# ElectronThingyStick.net
KiCad netlist of a schematic drawn in EAGLE
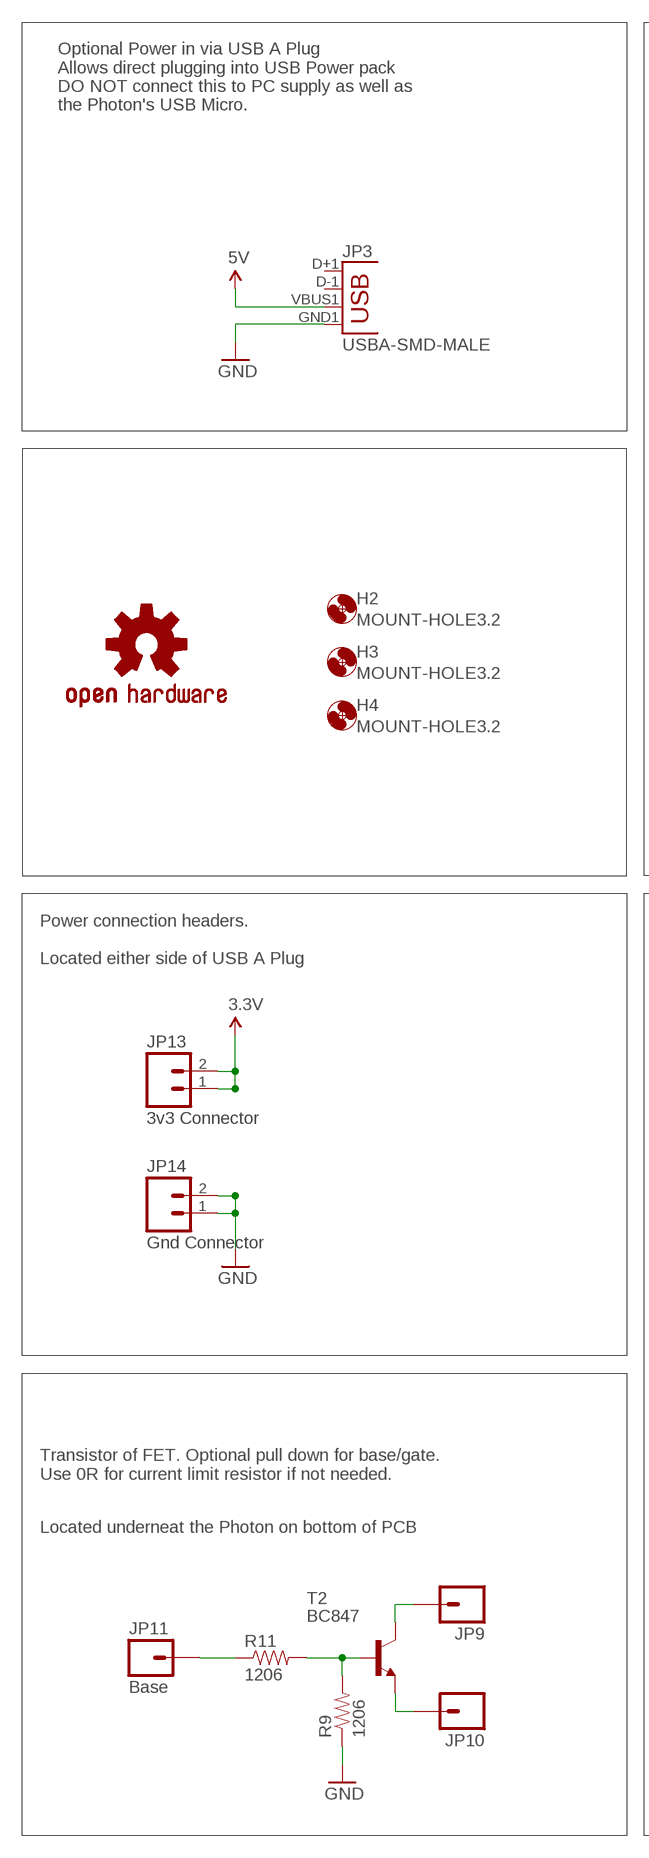
[diagram p0: schematic, sheet 1, part 1 of 2]
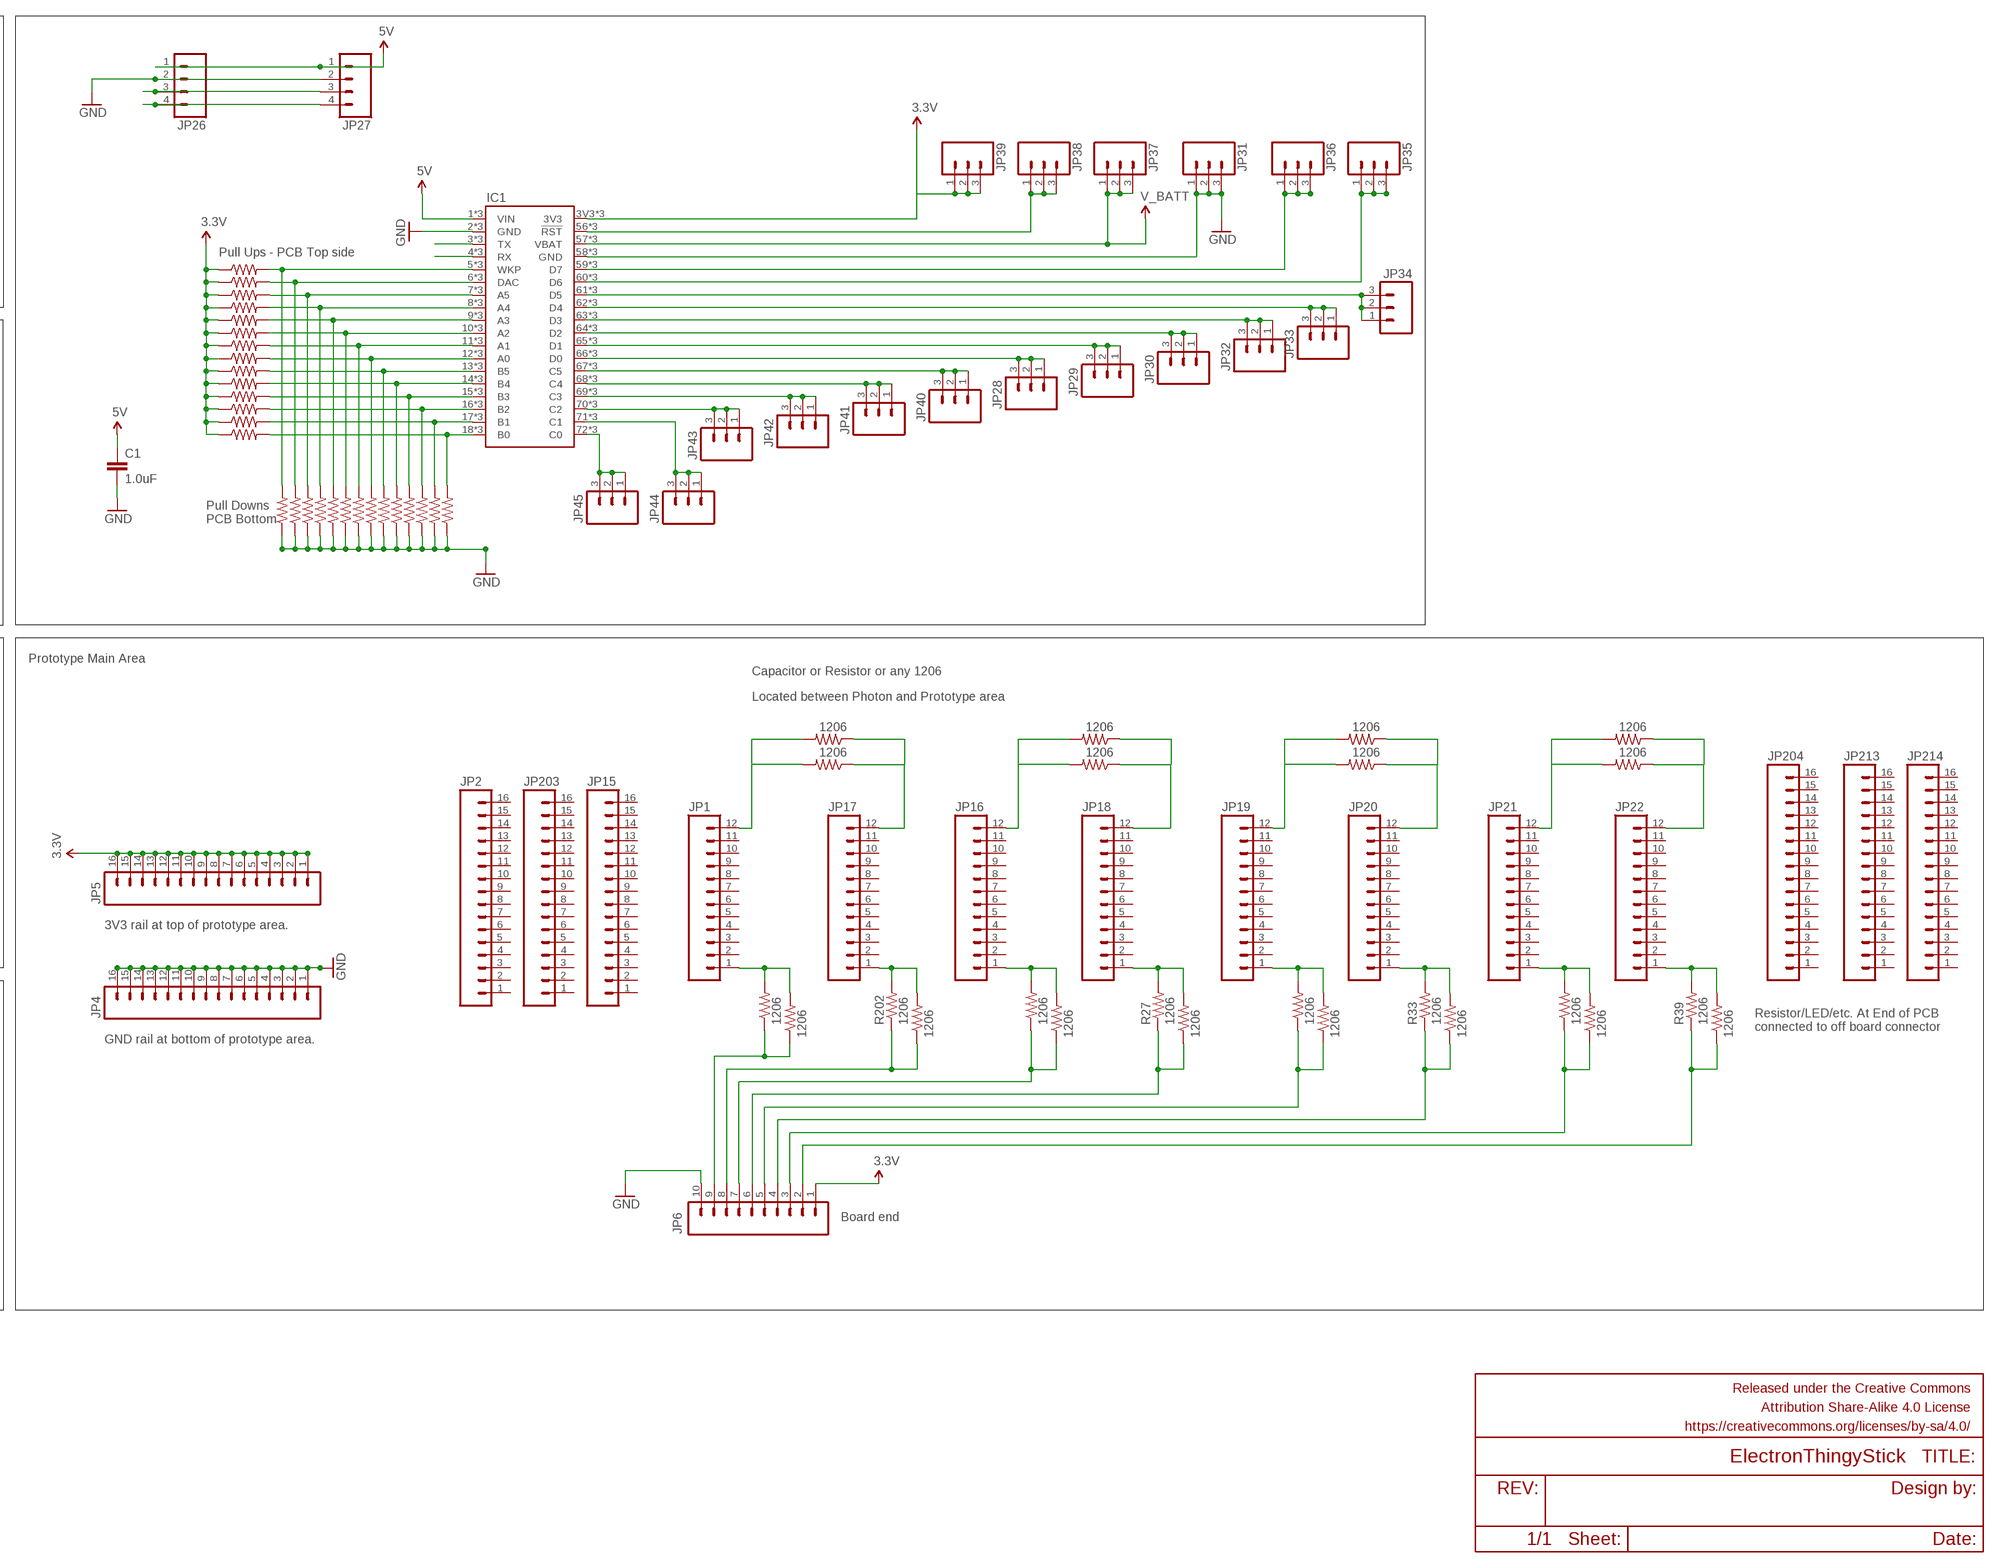
[diagram p1: schematic, sheet 1, part 2 of 2]

(export (version "E")
  (design (tool "Eeschema 10.0.6"))
  (components
    (comp (ref "C1")
      (value "1.0uF")
      (footprint "eagle-import:0805-CAP")
      (libsource (lib "eagle-import") (part "1.0UF-25V-+80/-20(0805){dblquote}"))
    )
    (comp (ref "FRAME1")
      (value "FRAME-LEDGER")
      (footprint "eagle-import:CREATIVE_COMMONS")
      (libsource (lib "eagle-import") (part "FRAME-LEDGER"))
    )
    (comp (ref "H2")
      (value "MOUNT-HOLE3.2")
      (footprint "eagle-import:3,2")
      (libsource (lib "eagle-import") (part "MOUNT-HOLE3.2"))
    )
    (comp (ref "H3")
      (value "MOUNT-HOLE3.2")
      (footprint "eagle-import:3,2")
      (libsource (lib "eagle-import") (part "MOUNT-HOLE3.2"))
    )
    (comp (ref "H4")
      (value "MOUNT-HOLE3.2")
      (footprint "eagle-import:3,2")
      (libsource (lib "eagle-import") (part "MOUNT-HOLE3.2"))
    )
    (comp (ref "IC1")
      (value "ELECTRONDUALROW")
      (footprint "eagle-import:ELECTRON_DUAL-ROW")
      (libsource (lib "eagle-import") (part "ELECTRONDUALROW"))
    )
    (comp (ref "JP1")
      (value "M12NO_SILK")
      (footprint "eagle-import:1X12_NO_SILK")
      (libsource (lib "eagle-import") (part "M12NO_SILK"))
    )
    (comp (ref "JP2")
      (value "M161X16_NO_SILK")
      (footprint "eagle-import:1X16_NO_SILK")
      (libsource (lib "eagle-import") (part "M161X16_NO_SILK"))
    )
    (comp (ref "JP3")
      (value "USBA-SMD-MALE")
      (footprint "eagle-import:USB-A-SMT-MALE")
      (libsource (lib "eagle-import") (part "USBA-SMD-MALE"))
    )
    (comp (ref "JP4")
      (value "M16PTH")
      (footprint "eagle-import:1X16")
      (libsource (lib "eagle-import") (part "M16PTH"))
    )
    (comp (ref "JP5")
      (value "M16PTH")
      (footprint "eagle-import:1X16")
      (libsource (lib "eagle-import") (part "M16PTH"))
    )
    (comp (ref "JP6")
      (value "M10NO_SILK_PTH_FEMALE")
      (footprint "eagle-import:1X10_NO_SILK")
      (libsource (lib "eagle-import") (part "M10NO_SILK_PTH_FEMALE"))
    )
    (comp (ref "JP9")
      (value "M01PTH")
      (footprint "eagle-import:1X01")
      (libsource (lib "eagle-import") (part "M01PTH"))
    )
    (comp (ref "JP10")
      (value "M01PTH")
      (footprint "eagle-import:1X01")
      (libsource (lib "eagle-import") (part "M01PTH"))
    )
    (comp (ref "JP11")
      (value "Base")
      (footprint "eagle-import:1X01")
      (libsource (lib "eagle-import") (part "M01PTH"))
    )
    (comp (ref "JP13")
      (value "3v3 Connector")
      (footprint "eagle-import:1X02")
      (libsource (lib "eagle-import") (part "M02PTH"))
    )
    (comp (ref "JP14")
      (value "Gnd Connector")
      (footprint "eagle-import:1X02")
      (libsource (lib "eagle-import") (part "M02PTH"))
    )
    (comp (ref "JP15")
      (value "M161X16_NO_SILK")
      (footprint "eagle-import:1X16_NO_SILK")
      (libsource (lib "eagle-import") (part "M161X16_NO_SILK"))
    )
    (comp (ref "JP16")
      (value "M12NO_SILK")
      (footprint "eagle-import:1X12_NO_SILK")
      (libsource (lib "eagle-import") (part "M12NO_SILK"))
    )
    (comp (ref "JP17")
      (value "M12NO_SILK")
      (footprint "eagle-import:1X12_NO_SILK")
      (libsource (lib "eagle-import") (part "M12NO_SILK"))
    )
    (comp (ref "JP18")
      (value "M12NO_SILK")
      (footprint "eagle-import:1X12_NO_SILK")
      (libsource (lib "eagle-import") (part "M12NO_SILK"))
    )
    (comp (ref "JP19")
      (value "M12NO_SILK")
      (footprint "eagle-import:1X12_NO_SILK")
      (libsource (lib "eagle-import") (part "M12NO_SILK"))
    )
    (comp (ref "JP20")
      (value "M12NO_SILK")
      (footprint "eagle-import:1X12_NO_SILK")
      (libsource (lib "eagle-import") (part "M12NO_SILK"))
    )
    (comp (ref "JP21")
      (value "M12NO_SILK")
      (footprint "eagle-import:1X12_NO_SILK")
      (libsource (lib "eagle-import") (part "M12NO_SILK"))
    )
    (comp (ref "JP22")
      (value "M12NO_SILK")
      (footprint "eagle-import:1X12_NO_SILK")
      (libsource (lib "eagle-import") (part "M12NO_SILK"))
    )
    (comp (ref "JP26")
      (value "M041X04_NO_SILK")
      (footprint "eagle-import:1X04_NO_SILK")
      (libsource (lib "eagle-import") (part "M041X04_NO_SILK"))
    )
    (comp (ref "JP27")
      (value "M041X04_NO_SILK")
      (footprint "eagle-import:1X04_NO_SILK")
      (libsource (lib "eagle-import") (part "M041X04_NO_SILK"))
    )
    (comp (ref "JP28")
      (value "M03PTH")
      (footprint "eagle-import:1X03")
      (libsource (lib "eagle-import") (part "M03PTH"))
    )
    (comp (ref "JP29")
      (value "M03PTH")
      (footprint "eagle-import:1X03")
      (libsource (lib "eagle-import") (part "M03PTH"))
    )
    (comp (ref "JP30")
      (value "M03PTH")
      (footprint "eagle-import:1X03")
      (libsource (lib "eagle-import") (part "M03PTH"))
    )
    (comp (ref "JP31")
      (value "M03PTH")
      (footprint "eagle-import:1X03")
      (libsource (lib "eagle-import") (part "M03PTH"))
    )
    (comp (ref "JP32")
      (value "M03PTH")
      (footprint "eagle-import:1X03")
      (libsource (lib "eagle-import") (part "M03PTH"))
    )
    (comp (ref "JP33")
      (value "M03PTH")
      (footprint "eagle-import:1X03")
      (libsource (lib "eagle-import") (part "M03PTH"))
    )
    (comp (ref "JP34")
      (value "M03PTH")
      (footprint "eagle-import:1X03")
      (libsource (lib "eagle-import") (part "M03PTH"))
    )
    (comp (ref "JP35")
      (value "M03PTH")
      (footprint "eagle-import:1X03")
      (libsource (lib "eagle-import") (part "M03PTH"))
    )
    (comp (ref "JP36")
      (value "M03PTH")
      (footprint "eagle-import:1X03")
      (libsource (lib "eagle-import") (part "M03PTH"))
    )
    (comp (ref "JP37")
      (value "M03PTH")
      (footprint "eagle-import:1X03")
      (libsource (lib "eagle-import") (part "M03PTH"))
    )
    (comp (ref "JP38")
      (value "M03PTH")
      (footprint "eagle-import:1X03")
      (libsource (lib "eagle-import") (part "M03PTH"))
    )
    (comp (ref "JP39")
      (value "M03PTH")
      (footprint "eagle-import:1X03")
      (libsource (lib "eagle-import") (part "M03PTH"))
    )
    (comp (ref "JP40")
      (value "M03PTH")
      (footprint "eagle-import:1X03")
      (libsource (lib "eagle-import") (part "M03PTH"))
    )
    (comp (ref "JP41")
      (value "M03PTH")
      (footprint "eagle-import:1X03")
      (libsource (lib "eagle-import") (part "M03PTH"))
    )
    (comp (ref "JP42")
      (value "M03PTH")
      (footprint "eagle-import:1X03")
      (libsource (lib "eagle-import") (part "M03PTH"))
    )
    (comp (ref "JP43")
      (value "M03PTH")
      (footprint "eagle-import:1X03")
      (libsource (lib "eagle-import") (part "M03PTH"))
    )
    (comp (ref "JP44")
      (value "M03PTH")
      (footprint "eagle-import:1X03")
      (libsource (lib "eagle-import") (part "M03PTH"))
    )
    (comp (ref "JP45")
      (value "M03PTH")
      (footprint "eagle-import:1X03")
      (libsource (lib "eagle-import") (part "M03PTH"))
    )
    (comp (ref "JP203")
      (value "M161X16_NO_SILK")
      (footprint "eagle-import:1X16_NO_SILK")
      (libsource (lib "eagle-import") (part "M161X16_NO_SILK"))
    )
    (comp (ref "JP204")
      (value "M161X16_NO_SILK")
      (footprint "eagle-import:1X16_NO_SILK")
      (libsource (lib "eagle-import") (part "M161X16_NO_SILK"))
    )
    (comp (ref "JP213")
      (value "M161X16_NO_SILK")
      (footprint "eagle-import:1X16_NO_SILK")
      (libsource (lib "eagle-import") (part "M161X16_NO_SILK"))
    )
    (comp (ref "JP214")
      (value "M161X16_NO_SILK")
      (footprint "eagle-import:1X16_NO_SILK")
      (libsource (lib "eagle-import") (part "M161X16_NO_SILK"))
    )
    (comp (ref "LOGO1")
      (value "OSHW-LOGOM")
      (footprint "eagle-import:OSHW-LOGO-M")
      (libsource (lib "eagle-import") (part "OSHW-LOGOM"))
    )
    (comp (ref "R1")
      (value "1206")
      (footprint "eagle-import:1206")
      (libsource (lib "eagle-import") (part "SparkFun-Resistors_RESISTOR1206"))
    )
    (comp (ref "R2")
      (value "1206")
      (footprint "eagle-import:1206")
      (libsource (lib "eagle-import") (part "SparkFun-Resistors_RESISTOR1206"))
    )
    (comp (ref "R3")
      (value "1206")
      (footprint "eagle-import:1206")
      (libsource (lib "eagle-import") (part "SparkFun-Resistors_RESISTOR1206"))
    )
    (comp (ref "R4")
      (value "1206")
      (footprint "eagle-import:1206")
      (libsource (lib "eagle-import") (part "SparkFun-Resistors_RESISTOR1206"))
    )
    (comp (ref "R5")
      (value "1206")
      (footprint "eagle-import:1206")
      (libsource (lib "eagle-import") (part "SparkFun-Resistors_RESISTOR1206"))
    )
    (comp (ref "R6")
      (value "1206")
      (footprint "eagle-import:1206")
      (libsource (lib "eagle-import") (part "SparkFun-Resistors_RESISTOR1206"))
    )
    (comp (ref "R7")
      (value "1206")
      (footprint "eagle-import:1206")
      (libsource (lib "eagle-import") (part "SparkFun-Resistors_RESISTOR1206"))
    )
    (comp (ref "R8")
      (value "1206")
      (footprint "eagle-import:1206")
      (libsource (lib "eagle-import") (part "SparkFun-Resistors_RESISTOR1206"))
    )
    (comp (ref "R9")
      (value "1206")
      (footprint "eagle-import:1206")
      (libsource (lib "eagle-import") (part "RESISTOR1206"))
    )
    (comp (ref "R10")
      (value "1206")
      (footprint "eagle-import:1206")
      (libsource (lib "eagle-import") (part "SparkFun-Resistors_RESISTOR1206"))
    )
    (comp (ref "R11")
      (value "1206")
      (footprint "eagle-import:1206")
      (libsource (lib "eagle-import") (part "RESISTOR1206"))
    )
    (comp (ref "R12")
      (value "1206")
      (footprint "eagle-import:1206")
      (libsource (lib "eagle-import") (part "SparkFun-Resistors_RESISTOR1206"))
    )
    (comp (ref "R13")
      (value "1206")
      (footprint "eagle-import:1206")
      (libsource (lib "eagle-import") (part "SparkFun-Resistors_RESISTOR1206"))
    )
    (comp (ref "R14")
      (value "1206")
      (footprint "eagle-import:1206")
      (libsource (lib "eagle-import") (part "SparkFun-Resistors_RESISTOR1206"))
    )
    (comp (ref "R15")
      (value "1206")
      (footprint "eagle-import:1206")
      (libsource (lib "eagle-import") (part "SparkFun-Resistors_RESISTOR1206"))
    )
    (comp (ref "R16")
      (value "1206")
      (footprint "eagle-import:1206")
      (libsource (lib "eagle-import") (part "SparkFun-Resistors_RESISTOR1206"))
    )
    (comp (ref "R17")
      (value "1206")
      (footprint "eagle-import:1206")
      (libsource (lib "eagle-import") (part "SparkFun-Resistors_RESISTOR1206"))
    )
    (comp (ref "R18")
      (value "1206")
      (footprint "eagle-import:1206")
      (libsource (lib "eagle-import") (part "SparkFun-Resistors_RESISTOR1206"))
    )
    (comp (ref "R19")
      (value "1206")
      (footprint "eagle-import:1206")
      (libsource (lib "eagle-import") (part "SparkFun-Resistors_RESISTOR1206"))
    )
    (comp (ref "R20")
      (value "1206")
      (footprint "eagle-import:1206")
      (libsource (lib "eagle-import") (part "SparkFun-Resistors_RESISTOR1206"))
    )
    (comp (ref "R21")
      (value "1206")
      (footprint "eagle-import:1206")
      (libsource (lib "eagle-import") (part "SparkFun-Resistors_RESISTOR1206"))
    )
    (comp (ref "R22")
      (value "1206")
      (footprint "eagle-import:1206")
      (libsource (lib "eagle-import") (part "SparkFun-Resistors_RESISTOR1206"))
    )
    (comp (ref "R23")
      (value "1206")
      (footprint "eagle-import:1206")
      (libsource (lib "eagle-import") (part "SparkFun-Resistors_RESISTOR1206"))
    )
    (comp (ref "R24")
      (value "1206")
      (footprint "eagle-import:1206")
      (libsource (lib "eagle-import") (part "SparkFun-Resistors_RESISTOR1206"))
    )
    (comp (ref "R25")
      (value "1206")
      (footprint "eagle-import:1206")
      (libsource (lib "eagle-import") (part "SparkFun-Resistors_RESISTOR1206"))
    )
    (comp (ref "R26")
      (value "1206")
      (footprint "eagle-import:1206")
      (libsource (lib "eagle-import") (part "SparkFun-Resistors_RESISTOR1206"))
    )
    (comp (ref "R27")
      (value "1206")
      (footprint "eagle-import:1206")
      (libsource (lib "eagle-import") (part "SparkFun-Resistors_RESISTOR1206"))
    )
    (comp (ref "R28")
      (value "1206")
      (footprint "eagle-import:1206")
      (libsource (lib "eagle-import") (part "SparkFun-Resistors_RESISTOR1206"))
    )
    (comp (ref "R29")
      (value "1206")
      (footprint "eagle-import:1206")
      (libsource (lib "eagle-import") (part "SparkFun-Resistors_RESISTOR1206"))
    )
    (comp (ref "R30")
      (value "1206")
      (footprint "eagle-import:1206")
      (libsource (lib "eagle-import") (part "SparkFun-Resistors_RESISTOR1206"))
    )
    (comp (ref "R31")
      (value "1206")
      (footprint "eagle-import:1206")
      (libsource (lib "eagle-import") (part "SparkFun-Resistors_RESISTOR1206"))
    )
    (comp (ref "R32")
      (value "1206")
      (footprint "eagle-import:1206")
      (libsource (lib "eagle-import") (part "SparkFun-Resistors_RESISTOR1206"))
    )
    (comp (ref "R33")
      (value "1206")
      (footprint "eagle-import:1206")
      (libsource (lib "eagle-import") (part "SparkFun-Resistors_RESISTOR1206"))
    )
    (comp (ref "R34")
      (value "1206")
      (footprint "eagle-import:1206")
      (libsource (lib "eagle-import") (part "SparkFun-Resistors_RESISTOR1206"))
    )
    (comp (ref "R35")
      (value "1206")
      (footprint "eagle-import:1206")
      (libsource (lib "eagle-import") (part "SparkFun-Resistors_RESISTOR1206"))
    )
    (comp (ref "R36")
      (value "1206")
      (footprint "eagle-import:1206")
      (libsource (lib "eagle-import") (part "SparkFun-Resistors_RESISTOR1206"))
    )
    (comp (ref "R37")
      (value "1206")
      (footprint "eagle-import:1206")
      (libsource (lib "eagle-import") (part "SparkFun-Resistors_RESISTOR1206"))
    )
    (comp (ref "R38")
      (value "1206")
      (footprint "eagle-import:1206")
      (libsource (lib "eagle-import") (part "SparkFun-Resistors_RESISTOR1206"))
    )
    (comp (ref "R39")
      (value "1206")
      (footprint "eagle-import:1206")
      (libsource (lib "eagle-import") (part "SparkFun-Resistors_RESISTOR1206"))
    )
    (comp (ref "R40")
      (value "1206")
      (footprint "eagle-import:1206")
      (libsource (lib "eagle-import") (part "SparkFun-Resistors_RESISTOR1206"))
    )
    (comp (ref "R41")
      (value "1206")
      (footprint "eagle-import:1206")
      (libsource (lib "eagle-import") (part "SparkFun-Resistors_RESISTOR1206"))
    )
    (comp (ref "R42")
      (value "1206")
      (footprint "eagle-import:1206")
      (libsource (lib "eagle-import") (part "SparkFun-Resistors_RESISTOR1206"))
    )
    (comp (ref "R43")
      (value "1206")
      (footprint "eagle-import:1206")
      (libsource (lib "eagle-import") (part "SparkFun-Resistors_RESISTOR1206"))
    )
    (comp (ref "R44")
      (value "1206")
      (footprint "eagle-import:1206")
      (libsource (lib "eagle-import") (part "SparkFun-Resistors_RESISTOR1206"))
    )
    (comp (ref "R45")
      (value "1206")
      (footprint "eagle-import:1206")
      (libsource (lib "eagle-import") (part "SparkFun-Resistors_RESISTOR1206"))
    )
    (comp (ref "R46")
      (value "1206")
      (footprint "eagle-import:1206")
      (libsource (lib "eagle-import") (part "SparkFun-Resistors_RESISTOR1206"))
    )
    (comp (ref "R47")
      (value "1206")
      (footprint "eagle-import:1206")
      (libsource (lib "eagle-import") (part "SparkFun-Resistors_RESISTOR1206"))
    )
    (comp (ref "R48")
      (value "1206")
      (footprint "eagle-import:1206")
      (libsource (lib "eagle-import") (part "SparkFun-Resistors_RESISTOR1206"))
    )
    (comp (ref "R49")
      (value "1206")
      (footprint "eagle-import:1206")
      (libsource (lib "eagle-import") (part "SparkFun-Resistors_RESISTOR1206"))
    )
    (comp (ref "R50")
      (value "1206")
      (footprint "eagle-import:1206")
      (libsource (lib "eagle-import") (part "SparkFun-Resistors_RESISTOR1206"))
    )
    (comp (ref "R51")
      (value "1206")
      (footprint "eagle-import:1206")
      (libsource (lib "eagle-import") (part "SparkFun-Resistors_RESISTOR1206"))
    )
    (comp (ref "R52")
      (value "1206")
      (footprint "eagle-import:1206")
      (libsource (lib "eagle-import") (part "SparkFun-Resistors_RESISTOR1206"))
    )
    (comp (ref "R201")
      (value "1206")
      (footprint "eagle-import:1206")
      (libsource (lib "eagle-import") (part "SparkFun-Resistors_RESISTOR1206"))
    )
    (comp (ref "R202")
      (value "1206")
      (footprint "eagle-import:1206")
      (libsource (lib "eagle-import") (part "SparkFun-Resistors_RESISTOR1206"))
    )
    (comp (ref "T2")
      (value "BC847")
      (footprint "eagle-import:SOT23")
      (libsource (lib "eagle-import") (part "BC847"))
    )
  )
  (nets
    (net (code "1") (name "/RX") (class "Default")
      (node (ref "IC1") (pin "4") (pinfunction "RX_4") (pintype "bidirectional"))
      (node (ref "IC1") (pin "40") (pinfunction "RX_40") (pintype "bidirectional"))
      (node (ref "IC1") (pin "RX") (pinfunction "RX_RX") (pintype "bidirectional"))
      (node (ref "JP26") (pin "4") (pinfunction "4_4") (pintype "passive"))
      (node (ref "JP27") (pin "4") (pinfunction "4_4") (pintype "passive"))
    )
    (net (code "2") (name "/TX") (class "Default")
      (node (ref "IC1") (pin "3") (pinfunction "TX_3") (pintype "bidirectional"))
      (node (ref "IC1") (pin "39") (pinfunction "TX_39") (pintype "bidirectional"))
      (node (ref "IC1") (pin "TX") (pinfunction "TX_TX") (pintype "bidirectional"))
      (node (ref "JP26") (pin "3") (pinfunction "3_3") (pintype "passive"))
      (node (ref "JP27") (pin "3") (pinfunction "3_3") (pintype "passive"))
    )
    (net (code "3") (name "3.3V") (class "Default")
      (node (ref "IC1") (pin "3V3") (pinfunction "3V3_3V3") (pintype "power_in"))
      (node (ref "IC1") (pin "55") (pinfunction "3V3_55") (pintype "power_in"))
      (node (ref "IC1") (pin "91") (pinfunction "3V3_91") (pintype "power_in"))
      (node (ref "JP13") (pin "1") (pinfunction "1_1") (pintype "passive"))
      (node (ref "JP13") (pin "2") (pinfunction "2_2") (pintype "passive"))
      (node (ref "JP39") (pin "1") (pinfunction "1_1") (pintype "passive"))
      (node (ref "JP39") (pin "2") (pinfunction "2_2") (pintype "passive"))
      (node (ref "JP39") (pin "3") (pinfunction "3_3") (pintype "passive"))
      (node (ref "JP5") (pin "1") (pinfunction "1_1") (pintype "passive"))
      (node (ref "JP5") (pin "10") (pinfunction "10_10") (pintype "passive"))
      (node (ref "JP5") (pin "11") (pinfunction "11_11") (pintype "passive"))
      (node (ref "JP5") (pin "12") (pinfunction "12_12") (pintype "passive"))
      (node (ref "JP5") (pin "13") (pinfunction "13_13") (pintype "passive"))
      (node (ref "JP5") (pin "14") (pinfunction "14_14") (pintype "passive"))
      (node (ref "JP5") (pin "15") (pinfunction "15_15") (pintype "passive"))
      (node (ref "JP5") (pin "16") (pinfunction "16_16") (pintype "passive"))
      (node (ref "JP5") (pin "2") (pinfunction "2_2") (pintype "passive"))
      (node (ref "JP5") (pin "3") (pinfunction "3_3") (pintype "passive"))
      (node (ref "JP5") (pin "4") (pinfunction "4_4") (pintype "passive"))
      (node (ref "JP5") (pin "5") (pinfunction "5_5") (pintype "passive"))
      (node (ref "JP5") (pin "6") (pinfunction "6_6") (pintype "passive"))
      (node (ref "JP5") (pin "7") (pinfunction "7_7") (pintype "passive"))
      (node (ref "JP5") (pin "8") (pinfunction "8_8") (pintype "passive"))
      (node (ref "JP5") (pin "9") (pinfunction "9_9") (pintype "passive"))
      (node (ref "JP6") (pin "1") (pinfunction "1_1") (pintype "passive"))
      (node (ref "R1") (pin "1") (pinfunction "1_1") (pintype "passive"))
      (node (ref "R12") (pin "1") (pinfunction "1_1") (pintype "passive"))
      (node (ref "R15") (pin "1") (pinfunction "1_1") (pintype "passive"))
      (node (ref "R16") (pin "1") (pinfunction "1_1") (pintype "passive"))
      (node (ref "R17") (pin "1") (pinfunction "1_1") (pintype "passive"))
      (node (ref "R18") (pin "1") (pinfunction "1_1") (pintype "passive"))
      (node (ref "R2") (pin "1") (pinfunction "1_1") (pintype "passive"))
      (node (ref "R3") (pin "1") (pinfunction "1_1") (pintype "passive"))
      (node (ref "R4") (pin "1") (pinfunction "1_1") (pintype "passive"))
      (node (ref "R45") (pin "1") (pinfunction "1_1") (pintype "passive"))
      (node (ref "R46") (pin "1") (pinfunction "1_1") (pintype "passive"))
      (node (ref "R5") (pin "1") (pinfunction "1_1") (pintype "passive"))
      (node (ref "R6") (pin "1") (pinfunction "1_1") (pintype "passive"))
      (node (ref "R7") (pin "1") (pinfunction "1_1") (pintype "passive"))
    )
    (net (code "4") (name "5V") (class "Default")
      (node (ref "C1") (pin "1") (pinfunction "1_1") (pintype "passive"))
      (node (ref "IC1") (pin "1") (pinfunction "VIN_1") (pintype "power_in"))
      (node (ref "IC1") (pin "37") (pinfunction "VIN_37") (pintype "power_in"))
      (node (ref "IC1") (pin "VIN") (pinfunction "VIN_VIN") (pintype "power_in"))
      (node (ref "JP26") (pin "1") (pinfunction "1_1") (pintype "passive"))
      (node (ref "JP27") (pin "1") (pinfunction "1_1") (pintype "passive"))
      (node (ref "JP3") (pin "VBUS1") (pinfunction "VBUS_VBUS1") (pintype "bidirectional"))
    )
    (net (code "5") (name "GND") (class "Default")
      (node (ref "C1") (pin "2") (pinfunction "2_2") (pintype "passive"))
      (node (ref "IC1") (pin "2") (pinfunction "GND_2") (pintype "power_in"))
      (node (ref "IC1") (pin "38") (pinfunction "GND_38") (pintype "power_in"))
      (node (ref "IC1") (pin "58") (pinfunction "GND_58") (pintype "power_in"))
      (node (ref "IC1") (pin "94") (pinfunction "GND_94") (pintype "power_in"))
      (node (ref "IC1") (pin "GND") (pinfunction "GND_GND") (pintype "power_in"))
      (node (ref "IC1") (pin "GND@2") (pinfunction "GND_GND@2") (pintype "power_in"))
      (node (ref "JP14") (pin "1") (pinfunction "1_1") (pintype "passive"))
      (node (ref "JP14") (pin "2") (pinfunction "2_2") (pintype "passive"))
      (node (ref "JP26") (pin "2") (pinfunction "2_2") (pintype "passive"))
      (node (ref "JP27") (pin "2") (pinfunction "2_2") (pintype "passive"))
      (node (ref "JP3") (pin "GND1") (pinfunction "GND_GND1") (pintype "bidirectional"))
      (node (ref "JP31") (pin "1") (pinfunction "1_1") (pintype "passive"))
      (node (ref "JP31") (pin "2") (pinfunction "2_2") (pintype "passive"))
      (node (ref "JP31") (pin "3") (pinfunction "3_3") (pintype "passive"))
      (node (ref "JP4") (pin "1") (pinfunction "1_1") (pintype "passive"))
      (node (ref "JP4") (pin "10") (pinfunction "10_10") (pintype "passive"))
      (node (ref "JP4") (pin "11") (pinfunction "11_11") (pintype "passive"))
      (node (ref "JP4") (pin "12") (pinfunction "12_12") (pintype "passive"))
      (node (ref "JP4") (pin "13") (pinfunction "13_13") (pintype "passive"))
      (node (ref "JP4") (pin "14") (pinfunction "14_14") (pintype "passive"))
      (node (ref "JP4") (pin "15") (pinfunction "15_15") (pintype "passive"))
      (node (ref "JP4") (pin "16") (pinfunction "16_16") (pintype "passive"))
      (node (ref "JP4") (pin "2") (pinfunction "2_2") (pintype "passive"))
      (node (ref "JP4") (pin "3") (pinfunction "3_3") (pintype "passive"))
      (node (ref "JP4") (pin "4") (pinfunction "4_4") (pintype "passive"))
      (node (ref "JP4") (pin "5") (pinfunction "5_5") (pintype "passive"))
      (node (ref "JP4") (pin "6") (pinfunction "6_6") (pintype "passive"))
      (node (ref "JP4") (pin "7") (pinfunction "7_7") (pintype "passive"))
      (node (ref "JP4") (pin "8") (pinfunction "8_8") (pintype "passive"))
      (node (ref "JP4") (pin "9") (pinfunction "9_9") (pintype "passive"))
      (node (ref "JP6") (pin "10") (pinfunction "10_10") (pintype "passive"))
      (node (ref "R10") (pin "1") (pinfunction "1_1") (pintype "passive"))
      (node (ref "R13") (pin "1") (pinfunction "1_1") (pintype "passive"))
      (node (ref "R14") (pin "1") (pinfunction "1_1") (pintype "passive"))
      (node (ref "R19") (pin "1") (pinfunction "1_1") (pintype "passive"))
      (node (ref "R20") (pin "1") (pinfunction "1_1") (pintype "passive"))
      (node (ref "R21") (pin "1") (pinfunction "1_1") (pintype "passive"))
      (node (ref "R22") (pin "1") (pinfunction "1_1") (pintype "passive"))
      (node (ref "R47") (pin "1") (pinfunction "1_1") (pintype "passive"))
      (node (ref "R48") (pin "1") (pinfunction "1_1") (pintype "passive"))
      (node (ref "R49") (pin "1") (pinfunction "1_1") (pintype "passive"))
      (node (ref "R50") (pin "1") (pinfunction "1_1") (pintype "passive"))
      (node (ref "R51") (pin "1") (pinfunction "1_1") (pintype "passive"))
      (node (ref "R52") (pin "1") (pinfunction "1_1") (pintype "passive"))
      (node (ref "R8") (pin "1") (pinfunction "1_1") (pintype "passive"))
      (node (ref "R9") (pin "1") (pinfunction "1_1") (pintype "passive"))
    )
    (net (code "6") (name "Net-(IC1-A0-Pad12)") (class "Default")
      (node (ref "IC1") (pin "12") (pinfunction "A0_12") (pintype "bidirectional"))
      (node (ref "IC1") (pin "48") (pinfunction "A0_48") (pintype "bidirectional"))
      (node (ref "IC1") (pin "A0") (pinfunction "A0_A0") (pintype "bidirectional"))
      (node (ref "R22") (pin "2") (pinfunction "2_2") (pintype "passive"))
      (node (ref "R7") (pin "2") (pinfunction "2_2") (pintype "passive"))
    )
    (net (code "7") (name "Net-(IC1-A1-Pad11)") (class "Default")
      (node (ref "IC1") (pin "11") (pinfunction "A1_11") (pintype "bidirectional"))
      (node (ref "IC1") (pin "47") (pinfunction "A1_47") (pintype "bidirectional"))
      (node (ref "IC1") (pin "A1") (pinfunction "A1_A1") (pintype "bidirectional"))
      (node (ref "R21") (pin "2") (pinfunction "2_2") (pintype "passive"))
      (node (ref "R6") (pin "2") (pinfunction "2_2") (pintype "passive"))
    )
    (net (code "8") (name "Net-(IC1-A2-Pad10)") (class "Default")
      (node (ref "IC1") (pin "10") (pinfunction "A2_10") (pintype "bidirectional"))
      (node (ref "IC1") (pin "46") (pinfunction "A2_46") (pintype "bidirectional"))
      (node (ref "IC1") (pin "A2") (pinfunction "A2_A2") (pintype "bidirectional"))
      (node (ref "R20") (pin "2") (pinfunction "2_2") (pintype "passive"))
      (node (ref "R4") (pin "2") (pinfunction "2_2") (pintype "passive"))
    )
    (net (code "9") (name "Net-(IC1-A3-Pad45)") (class "Default")
      (node (ref "IC1") (pin "45") (pinfunction "A3_45") (pintype "bidirectional"))
      (node (ref "IC1") (pin "9") (pinfunction "A3_9") (pintype "bidirectional"))
      (node (ref "IC1") (pin "A3") (pinfunction "A3_A3") (pintype "bidirectional"))
      (node (ref "R19") (pin "2") (pinfunction "2_2") (pintype "passive"))
      (node (ref "R3") (pin "2") (pinfunction "2_2") (pintype "passive"))
    )
    (net (code "10") (name "Net-(IC1-A4-Pad44)") (class "Default")
      (node (ref "IC1") (pin "44") (pinfunction "A4_44") (pintype "bidirectional"))
      (node (ref "IC1") (pin "8") (pinfunction "A4_8") (pintype "bidirectional"))
      (node (ref "IC1") (pin "A4") (pinfunction "A4_A4") (pintype "bidirectional"))
      (node (ref "R14") (pin "2") (pinfunction "2_2") (pintype "passive"))
      (node (ref "R2") (pin "2") (pinfunction "2_2") (pintype "passive"))
    )
    (net (code "11") (name "Net-(IC1-A5-Pad43)") (class "Default")
      (node (ref "IC1") (pin "43") (pinfunction "A5_43") (pintype "bidirectional"))
      (node (ref "IC1") (pin "7") (pinfunction "A5_7") (pintype "bidirectional"))
      (node (ref "IC1") (pin "A5") (pinfunction "A5_A5") (pintype "bidirectional"))
      (node (ref "R1") (pin "2") (pinfunction "2_2") (pintype "passive"))
      (node (ref "R13") (pin "2") (pinfunction "2_2") (pintype "passive"))
    )
    (net (code "12") (name "Net-(IC1-B0-Pad18)") (class "Default")
      (node (ref "IC1") (pin "18") (pinfunction "B0_18") (pintype "bidirectional"))
      (node (ref "IC1") (pin "54") (pinfunction "B0_54") (pintype "bidirectional"))
      (node (ref "IC1") (pin "B0") (pinfunction "B0_B0") (pintype "bidirectional"))
      (node (ref "R46") (pin "2") (pinfunction "2_2") (pintype "passive"))
      (node (ref "R52") (pin "2") (pinfunction "2_2") (pintype "passive"))
    )
    (net (code "13") (name "Net-(IC1-B1-Pad17)") (class "Default")
      (node (ref "IC1") (pin "17") (pinfunction "B1_17") (pintype "bidirectional"))
      (node (ref "IC1") (pin "53") (pinfunction "B1_53") (pintype "bidirectional"))
      (node (ref "IC1") (pin "B1") (pinfunction "B1_B1") (pintype "bidirectional"))
      (node (ref "R45") (pin "2") (pinfunction "2_2") (pintype "passive"))
      (node (ref "R51") (pin "2") (pinfunction "2_2") (pintype "passive"))
    )
    (net (code "14") (name "Net-(IC1-B2-Pad16)") (class "Default")
      (node (ref "IC1") (pin "16") (pinfunction "B2_16") (pintype "bidirectional"))
      (node (ref "IC1") (pin "52") (pinfunction "B2_52") (pintype "bidirectional"))
      (node (ref "IC1") (pin "B2") (pinfunction "B2_B2") (pintype "bidirectional"))
      (node (ref "R18") (pin "2") (pinfunction "2_2") (pintype "passive"))
      (node (ref "R50") (pin "2") (pinfunction "2_2") (pintype "passive"))
    )
    (net (code "15") (name "Net-(IC1-B3-Pad15)") (class "Default")
      (node (ref "IC1") (pin "15") (pinfunction "B3_15") (pintype "bidirectional"))
      (node (ref "IC1") (pin "51") (pinfunction "B3_51") (pintype "bidirectional"))
      (node (ref "IC1") (pin "B3") (pinfunction "B3_B3") (pintype "bidirectional"))
      (node (ref "R17") (pin "2") (pinfunction "2_2") (pintype "passive"))
      (node (ref "R49") (pin "2") (pinfunction "2_2") (pintype "passive"))
    )
    (net (code "16") (name "Net-(IC1-B4-Pad14)") (class "Default")
      (node (ref "IC1") (pin "14") (pinfunction "B4_14") (pintype "bidirectional"))
      (node (ref "IC1") (pin "50") (pinfunction "B4_50") (pintype "bidirectional"))
      (node (ref "IC1") (pin "B4") (pinfunction "B4_B4") (pintype "bidirectional"))
      (node (ref "R16") (pin "2") (pinfunction "2_2") (pintype "passive"))
      (node (ref "R48") (pin "2") (pinfunction "2_2") (pintype "passive"))
    )
    (net (code "17") (name "Net-(IC1-B5-Pad13)") (class "Default")
      (node (ref "IC1") (pin "13") (pinfunction "B5_13") (pintype "bidirectional"))
      (node (ref "IC1") (pin "49") (pinfunction "B5_49") (pintype "bidirectional"))
      (node (ref "IC1") (pin "B5") (pinfunction "B5_B5") (pintype "bidirectional"))
      (node (ref "R15") (pin "2") (pinfunction "2_2") (pintype "passive"))
      (node (ref "R47") (pin "2") (pinfunction "2_2") (pintype "passive"))
    )
    (net (code "18") (name "Net-(IC1-C0-Pad108)") (class "Default")
      (node (ref "IC1") (pin "108") (pinfunction "C0_108") (pintype "bidirectional"))
      (node (ref "IC1") (pin "72") (pinfunction "C0_72") (pintype "bidirectional"))
      (node (ref "IC1") (pin "C0") (pinfunction "C0_C0") (pintype "bidirectional"))
      (node (ref "JP45") (pin "1") (pinfunction "1_1") (pintype "passive"))
      (node (ref "JP45") (pin "2") (pinfunction "2_2") (pintype "passive"))
      (node (ref "JP45") (pin "3") (pinfunction "3_3") (pintype "passive"))
    )
    (net (code "19") (name "Net-(IC1-C1-Pad107)") (class "Default")
      (node (ref "IC1") (pin "107") (pinfunction "C1_107") (pintype "bidirectional"))
      (node (ref "IC1") (pin "71") (pinfunction "C1_71") (pintype "bidirectional"))
      (node (ref "IC1") (pin "C1") (pinfunction "C1_C1") (pintype "bidirectional"))
      (node (ref "JP44") (pin "1") (pinfunction "1_1") (pintype "passive"))
      (node (ref "JP44") (pin "2") (pinfunction "2_2") (pintype "passive"))
      (node (ref "JP44") (pin "3") (pinfunction "3_3") (pintype "passive"))
    )
    (net (code "20") (name "Net-(IC1-C2-Pad106)") (class "Default")
      (node (ref "IC1") (pin "106") (pinfunction "C2_106") (pintype "bidirectional"))
      (node (ref "IC1") (pin "70") (pinfunction "C2_70") (pintype "bidirectional"))
      (node (ref "IC1") (pin "C2") (pinfunction "C2_C2") (pintype "bidirectional"))
      (node (ref "JP43") (pin "1") (pinfunction "1_1") (pintype "passive"))
      (node (ref "JP43") (pin "2") (pinfunction "2_2") (pintype "passive"))
      (node (ref "JP43") (pin "3") (pinfunction "3_3") (pintype "passive"))
    )
    (net (code "21") (name "Net-(IC1-C3-Pad105)") (class "Default")
      (node (ref "IC1") (pin "105") (pinfunction "C3_105") (pintype "bidirectional"))
      (node (ref "IC1") (pin "69") (pinfunction "C3_69") (pintype "bidirectional"))
      (node (ref "IC1") (pin "C3") (pinfunction "C3_C3") (pintype "bidirectional"))
      (node (ref "JP42") (pin "1") (pinfunction "1_1") (pintype "passive"))
      (node (ref "JP42") (pin "2") (pinfunction "2_2") (pintype "passive"))
      (node (ref "JP42") (pin "3") (pinfunction "3_3") (pintype "passive"))
    )
    (net (code "22") (name "Net-(IC1-C4-Pad104)") (class "Default")
      (node (ref "IC1") (pin "104") (pinfunction "C4_104") (pintype "bidirectional"))
      (node (ref "IC1") (pin "68") (pinfunction "C4_68") (pintype "bidirectional"))
      (node (ref "IC1") (pin "C4") (pinfunction "C4_C4") (pintype "bidirectional"))
      (node (ref "JP41") (pin "1") (pinfunction "1_1") (pintype "passive"))
      (node (ref "JP41") (pin "2") (pinfunction "2_2") (pintype "passive"))
      (node (ref "JP41") (pin "3") (pinfunction "3_3") (pintype "passive"))
    )
    (net (code "23") (name "Net-(IC1-C5-Pad103)") (class "Default")
      (node (ref "IC1") (pin "103") (pinfunction "C5_103") (pintype "bidirectional"))
      (node (ref "IC1") (pin "67") (pinfunction "C5_67") (pintype "bidirectional"))
      (node (ref "IC1") (pin "C5") (pinfunction "C5_C5") (pintype "bidirectional"))
      (node (ref "JP40") (pin "1") (pinfunction "1_1") (pintype "passive"))
      (node (ref "JP40") (pin "2") (pinfunction "2_2") (pintype "passive"))
      (node (ref "JP40") (pin "3") (pinfunction "3_3") (pintype "passive"))
    )
    (net (code "24") (name "Net-(IC1-D0-Pad102)") (class "Default")
      (node (ref "IC1") (pin "102") (pinfunction "D0_102") (pintype "bidirectional"))
      (node (ref "IC1") (pin "66") (pinfunction "D0_66") (pintype "bidirectional"))
      (node (ref "IC1") (pin "D0") (pinfunction "D0_D0") (pintype "bidirectional"))
      (node (ref "JP28") (pin "1") (pinfunction "1_1") (pintype "passive"))
      (node (ref "JP28") (pin "2") (pinfunction "2_2") (pintype "passive"))
      (node (ref "JP28") (pin "3") (pinfunction "3_3") (pintype "passive"))
    )
    (net (code "25") (name "Net-(IC1-D1-Pad101)") (class "Default")
      (node (ref "IC1") (pin "101") (pinfunction "D1_101") (pintype "bidirectional"))
      (node (ref "IC1") (pin "65") (pinfunction "D1_65") (pintype "bidirectional"))
      (node (ref "IC1") (pin "D1") (pinfunction "D1_D1") (pintype "bidirectional"))
      (node (ref "JP29") (pin "1") (pinfunction "1_1") (pintype "passive"))
      (node (ref "JP29") (pin "2") (pinfunction "2_2") (pintype "passive"))
      (node (ref "JP29") (pin "3") (pinfunction "3_3") (pintype "passive"))
    )
    (net (code "26") (name "Net-(IC1-D2-Pad100)") (class "Default")
      (node (ref "IC1") (pin "100") (pinfunction "D2_100") (pintype "bidirectional"))
      (node (ref "IC1") (pin "64") (pinfunction "D2_64") (pintype "bidirectional"))
      (node (ref "IC1") (pin "D2") (pinfunction "D2_D2") (pintype "bidirectional"))
      (node (ref "JP30") (pin "1") (pinfunction "1_1") (pintype "passive"))
      (node (ref "JP30") (pin "2") (pinfunction "2_2") (pintype "passive"))
      (node (ref "JP30") (pin "3") (pinfunction "3_3") (pintype "passive"))
    )
    (net (code "27") (name "Net-(IC1-D3-Pad63)") (class "Default")
      (node (ref "IC1") (pin "63") (pinfunction "D3_63") (pintype "bidirectional"))
      (node (ref "IC1") (pin "99") (pinfunction "D3_99") (pintype "bidirectional"))
      (node (ref "IC1") (pin "D3") (pinfunction "D3_D3") (pintype "bidirectional"))
      (node (ref "JP32") (pin "1") (pinfunction "1_1") (pintype "passive"))
      (node (ref "JP32") (pin "2") (pinfunction "2_2") (pintype "passive"))
      (node (ref "JP32") (pin "3") (pinfunction "3_3") (pintype "passive"))
    )
    (net (code "28") (name "Net-(IC1-D4-Pad62)") (class "Default")
      (node (ref "IC1") (pin "62") (pinfunction "D4_62") (pintype "bidirectional"))
      (node (ref "IC1") (pin "98") (pinfunction "D4_98") (pintype "bidirectional"))
      (node (ref "IC1") (pin "D4") (pinfunction "D4_D4") (pintype "bidirectional"))
      (node (ref "JP33") (pin "1") (pinfunction "1_1") (pintype "passive"))
      (node (ref "JP33") (pin "2") (pinfunction "2_2") (pintype "passive"))
      (node (ref "JP33") (pin "3") (pinfunction "3_3") (pintype "passive"))
    )
    (net (code "29") (name "Net-(IC1-D5-Pad61)") (class "Default")
      (node (ref "IC1") (pin "61") (pinfunction "D5_61") (pintype "bidirectional"))
      (node (ref "IC1") (pin "97") (pinfunction "D5_97") (pintype "bidirectional"))
      (node (ref "IC1") (pin "D5") (pinfunction "D5_D5") (pintype "bidirectional"))
      (node (ref "JP34") (pin "1") (pinfunction "1_1") (pintype "passive"))
      (node (ref "JP34") (pin "2") (pinfunction "2_2") (pintype "passive"))
      (node (ref "JP34") (pin "3") (pinfunction "3_3") (pintype "passive"))
    )
    (net (code "30") (name "Net-(IC1-D6-Pad60)") (class "Default")
      (node (ref "IC1") (pin "60") (pinfunction "D6_60") (pintype "bidirectional"))
      (node (ref "IC1") (pin "96") (pinfunction "D6_96") (pintype "bidirectional"))
      (node (ref "IC1") (pin "D6") (pinfunction "D6_D6") (pintype "bidirectional"))
      (node (ref "JP35") (pin "1") (pinfunction "1_1") (pintype "passive"))
      (node (ref "JP35") (pin "2") (pinfunction "2_2") (pintype "passive"))
      (node (ref "JP35") (pin "3") (pinfunction "3_3") (pintype "passive"))
    )
    (net (code "31") (name "Net-(IC1-D7-Pad59)") (class "Default")
      (node (ref "IC1") (pin "59") (pinfunction "D7_59") (pintype "bidirectional"))
      (node (ref "IC1") (pin "95") (pinfunction "D7_95") (pintype "bidirectional"))
      (node (ref "IC1") (pin "D7") (pinfunction "D7_D7") (pintype "bidirectional"))
      (node (ref "JP36") (pin "1") (pinfunction "1_1") (pintype "passive"))
      (node (ref "JP36") (pin "2") (pinfunction "2_2") (pintype "passive"))
      (node (ref "JP36") (pin "3") (pinfunction "3_3") (pintype "passive"))
    )
    (net (code "32") (name "Net-(IC1-DAC-Pad42)") (class "Default")
      (node (ref "IC1") (pin "42") (pinfunction "DAC_42") (pintype "bidirectional"))
      (node (ref "IC1") (pin "6") (pinfunction "DAC_6") (pintype "bidirectional"))
      (node (ref "IC1") (pin "DAC") (pinfunction "DAC_DAC") (pintype "bidirectional"))
      (node (ref "R10") (pin "2") (pinfunction "2_2") (pintype "passive"))
      (node (ref "R5") (pin "2") (pinfunction "2_2") (pintype "passive"))
    )
    (net (code "33") (name "Net-(IC1-PadWKP)") (class "Default")
      (node (ref "IC1") (pin "41") (pinfunction "WKP_41") (pintype "bidirectional"))
      (node (ref "IC1") (pin "5") (pinfunction "WKP_5") (pintype "bidirectional"))
      (node (ref "IC1") (pin "WKP") (pinfunction "WKP_WKP") (pintype "bidirectional"))
      (node (ref "R12") (pin "2") (pinfunction "2_2") (pintype "passive"))
      (node (ref "R8") (pin "2") (pinfunction "2_2") (pintype "passive"))
    )
    (net (code "34") (name "Net-(IC1-~{RST}-Pad56)") (class "Default")
      (node (ref "IC1") (pin "56") (pinfunction "~{RST}_56") (pintype "bidirectional"))
      (node (ref "IC1") (pin "92") (pinfunction "~{RST}_92") (pintype "bidirectional"))
      (node (ref "IC1") (pin "RST") (pinfunction "~{RST}_RST") (pintype "bidirectional"))
      (node (ref "JP38") (pin "1") (pinfunction "1_1") (pintype "passive"))
      (node (ref "JP38") (pin "2") (pinfunction "2_2") (pintype "passive"))
      (node (ref "JP38") (pin "3") (pinfunction "3_3") (pintype "passive"))
    )
    (net (code "35") (name "Net-(JP1-Pad1)") (class "Default")
      (node (ref "JP1") (pin "1") (pinfunction "1_1") (pintype "passive"))
      (node (ref "R201") (pin "2") (pinfunction "2_2") (pintype "passive"))
      (node (ref "R23") (pin "2") (pinfunction "2_2") (pintype "passive"))
    )
    (net (code "36") (name "Net-(JP1-Pad12)") (class "Default")
      (node (ref "JP1") (pin "12") (pinfunction "12_12") (pintype "passive"))
      (node (ref "R24") (pin "2") (pinfunction "2_2") (pintype "passive"))
      (node (ref "R25") (pin "2") (pinfunction "2_2") (pintype "passive"))
    )
    (net (code "37") (name "Net-(JP6-Pad2)") (class "Default")
      (node (ref "JP6") (pin "2") (pinfunction "2_2") (pintype "passive"))
      (node (ref "R39") (pin "1") (pinfunction "1_1") (pintype "passive"))
      (node (ref "R44") (pin "1") (pinfunction "1_1") (pintype "passive"))
    )
    (net (code "38") (name "Net-(JP6-Pad3)") (class "Default")
      (node (ref "JP6") (pin "3") (pinfunction "3_3") (pintype "passive"))
      (node (ref "R40") (pin "1") (pinfunction "1_1") (pintype "passive"))
      (node (ref "R41") (pin "1") (pinfunction "1_1") (pintype "passive"))
    )
    (net (code "39") (name "Net-(JP6-Pad4)") (class "Default")
      (node (ref "JP6") (pin "4") (pinfunction "4_4") (pintype "passive"))
      (node (ref "R33") (pin "1") (pinfunction "1_1") (pintype "passive"))
      (node (ref "R38") (pin "1") (pinfunction "1_1") (pintype "passive"))
    )
    (net (code "40") (name "Net-(JP6-Pad5)") (class "Default")
      (node (ref "JP6") (pin "5") (pinfunction "5_5") (pintype "passive"))
      (node (ref "R34") (pin "1") (pinfunction "1_1") (pintype "passive"))
      (node (ref "R35") (pin "1") (pinfunction "1_1") (pintype "passive"))
    )
    (net (code "41") (name "Net-(JP6-Pad6)") (class "Default")
      (node (ref "JP6") (pin "6") (pinfunction "6_6") (pintype "passive"))
      (node (ref "R27") (pin "1") (pinfunction "1_1") (pintype "passive"))
      (node (ref "R32") (pin "1") (pinfunction "1_1") (pintype "passive"))
    )
    (net (code "42") (name "Net-(JP6-Pad7)") (class "Default")
      (node (ref "JP6") (pin "7") (pinfunction "7_7") (pintype "passive"))
      (node (ref "R28") (pin "1") (pinfunction "1_1") (pintype "passive"))
      (node (ref "R29") (pin "1") (pinfunction "1_1") (pintype "passive"))
    )
    (net (code "43") (name "Net-(JP6-Pad8)") (class "Default")
      (node (ref "JP6") (pin "8") (pinfunction "8_8") (pintype "passive"))
      (node (ref "R202") (pin "1") (pinfunction "1_1") (pintype "passive"))
      (node (ref "R26") (pin "1") (pinfunction "1_1") (pintype "passive"))
    )
    (net (code "44") (name "Net-(JP6-Pad9)") (class "Default")
      (node (ref "JP6") (pin "9") (pinfunction "9_9") (pintype "passive"))
      (node (ref "R201") (pin "1") (pinfunction "1_1") (pintype "passive"))
      (node (ref "R23") (pin "1") (pinfunction "1_1") (pintype "passive"))
    )
    (net (code "45") (name "Net-(JP11-Pad1)") (class "Default")
      (node (ref "JP11") (pin "1") (pinfunction "1_1") (pintype "passive"))
      (node (ref "R11") (pin "1") (pinfunction "1_1") (pintype "passive"))
    )
    (net (code "46") (name "Net-(JP16-Pad1)") (class "Default")
      (node (ref "JP16") (pin "1") (pinfunction "1_1") (pintype "passive"))
      (node (ref "R28") (pin "2") (pinfunction "2_2") (pintype "passive"))
      (node (ref "R29") (pin "2") (pinfunction "2_2") (pintype "passive"))
    )
    (net (code "47") (name "Net-(JP16-Pad12)") (class "Default")
      (node (ref "JP16") (pin "12") (pinfunction "12_12") (pintype "passive"))
      (node (ref "R30") (pin "2") (pinfunction "2_2") (pintype "passive"))
      (node (ref "R31") (pin "2") (pinfunction "2_2") (pintype "passive"))
    )
    (net (code "48") (name "Net-(JP17-Pad1)") (class "Default")
      (node (ref "JP17") (pin "1") (pinfunction "1_1") (pintype "passive"))
      (node (ref "R202") (pin "2") (pinfunction "2_2") (pintype "passive"))
      (node (ref "R26") (pin "2") (pinfunction "2_2") (pintype "passive"))
    )
    (net (code "49") (name "Net-(JP17-Pad12)") (class "Default")
      (node (ref "JP17") (pin "12") (pinfunction "12_12") (pintype "passive"))
      (node (ref "R24") (pin "1") (pinfunction "1_1") (pintype "passive"))
      (node (ref "R25") (pin "1") (pinfunction "1_1") (pintype "passive"))
    )
    (net (code "50") (name "Net-(JP18-Pad1)") (class "Default")
      (node (ref "JP18") (pin "1") (pinfunction "1_1") (pintype "passive"))
      (node (ref "R27") (pin "2") (pinfunction "2_2") (pintype "passive"))
      (node (ref "R32") (pin "2") (pinfunction "2_2") (pintype "passive"))
    )
    (net (code "51") (name "Net-(JP18-Pad12)") (class "Default")
      (node (ref "JP18") (pin "12") (pinfunction "12_12") (pintype "passive"))
      (node (ref "R30") (pin "1") (pinfunction "1_1") (pintype "passive"))
      (node (ref "R31") (pin "1") (pinfunction "1_1") (pintype "passive"))
    )
    (net (code "52") (name "Net-(JP19-Pad1)") (class "Default")
      (node (ref "JP19") (pin "1") (pinfunction "1_1") (pintype "passive"))
      (node (ref "R34") (pin "2") (pinfunction "2_2") (pintype "passive"))
      (node (ref "R35") (pin "2") (pinfunction "2_2") (pintype "passive"))
    )
    (net (code "53") (name "Net-(JP19-Pad12)") (class "Default")
      (node (ref "JP19") (pin "12") (pinfunction "12_12") (pintype "passive"))
      (node (ref "R36") (pin "2") (pinfunction "2_2") (pintype "passive"))
      (node (ref "R37") (pin "2") (pinfunction "2_2") (pintype "passive"))
    )
    (net (code "54") (name "Net-(JP20-Pad1)") (class "Default")
      (node (ref "JP20") (pin "1") (pinfunction "1_1") (pintype "passive"))
      (node (ref "R33") (pin "2") (pinfunction "2_2") (pintype "passive"))
      (node (ref "R38") (pin "2") (pinfunction "2_2") (pintype "passive"))
    )
    (net (code "55") (name "Net-(JP20-Pad12)") (class "Default")
      (node (ref "JP20") (pin "12") (pinfunction "12_12") (pintype "passive"))
      (node (ref "R36") (pin "1") (pinfunction "1_1") (pintype "passive"))
      (node (ref "R37") (pin "1") (pinfunction "1_1") (pintype "passive"))
    )
    (net (code "56") (name "Net-(JP21-Pad1)") (class "Default")
      (node (ref "JP21") (pin "1") (pinfunction "1_1") (pintype "passive"))
      (node (ref "R40") (pin "2") (pinfunction "2_2") (pintype "passive"))
      (node (ref "R41") (pin "2") (pinfunction "2_2") (pintype "passive"))
    )
    (net (code "57") (name "Net-(JP21-Pad12)") (class "Default")
      (node (ref "JP21") (pin "12") (pinfunction "12_12") (pintype "passive"))
      (node (ref "R42") (pin "2") (pinfunction "2_2") (pintype "passive"))
      (node (ref "R43") (pin "2") (pinfunction "2_2") (pintype "passive"))
    )
    (net (code "58") (name "Net-(JP22-Pad1)") (class "Default")
      (node (ref "JP22") (pin "1") (pinfunction "1_1") (pintype "passive"))
      (node (ref "R39") (pin "2") (pinfunction "2_2") (pintype "passive"))
      (node (ref "R44") (pin "2") (pinfunction "2_2") (pintype "passive"))
    )
    (net (code "59") (name "Net-(JP22-Pad12)") (class "Default")
      (node (ref "JP22") (pin "12") (pinfunction "12_12") (pintype "passive"))
      (node (ref "R42") (pin "1") (pinfunction "1_1") (pintype "passive"))
      (node (ref "R43") (pin "1") (pinfunction "1_1") (pintype "passive"))
    )
    (net (code "60") (name "Net-(T2-B)") (class "Default")
      (node (ref "R11") (pin "2") (pinfunction "2_2") (pintype "passive"))
      (node (ref "R9") (pin "2") (pinfunction "2_2") (pintype "passive"))
      (node (ref "T2") (pin "1") (pinfunction "B_1") (pintype "passive"))
    )
    (net (code "61") (name "Net-(T2-C)") (class "Default")
      (node (ref "JP9") (pin "1") (pinfunction "1_1") (pintype "passive"))
      (node (ref "T2") (pin "3") (pinfunction "C_3") (pintype "passive"))
    )
    (net (code "62") (name "Net-(T2-E)") (class "Default")
      (node (ref "JP10") (pin "1") (pinfunction "1_1") (pintype "passive"))
      (node (ref "T2") (pin "2") (pinfunction "E_2") (pintype "passive"))
    )
    (net (code "63") (name "V_BATT") (class "Default")
      (node (ref "IC1") (pin "57") (pinfunction "VBAT_57") (pintype "passive"))
      (node (ref "IC1") (pin "93") (pinfunction "VBAT_93") (pintype "passive"))
      (node (ref "IC1") (pin "VBAT") (pinfunction "VBAT_VBAT") (pintype "passive"))
      (node (ref "JP37") (pin "1") (pinfunction "1_1") (pintype "passive"))
      (node (ref "JP37") (pin "2") (pinfunction "2_2") (pintype "passive"))
      (node (ref "JP37") (pin "3") (pinfunction "3_3") (pintype "passive"))
    )
    (net (code "64") (name "unconnected-(JP1-Pad2)") (class "Default")
      (node (ref "JP1") (pin "2") (pinfunction "2_2") (pintype "passive"))
    )
    (net (code "65") (name "unconnected-(JP1-Pad3)") (class "Default")
      (node (ref "JP1") (pin "3") (pinfunction "3_3") (pintype "passive"))
    )
    (net (code "66") (name "unconnected-(JP1-Pad4)") (class "Default")
      (node (ref "JP1") (pin "4") (pinfunction "4_4") (pintype "passive"))
    )
    (net (code "67") (name "unconnected-(JP1-Pad5)") (class "Default")
      (node (ref "JP1") (pin "5") (pinfunction "5_5") (pintype "passive"))
    )
    (net (code "68") (name "unconnected-(JP1-Pad6)") (class "Default")
      (node (ref "JP1") (pin "6") (pinfunction "6_6") (pintype "passive"))
    )
    (net (code "69") (name "unconnected-(JP1-Pad7)") (class "Default")
      (node (ref "JP1") (pin "7") (pinfunction "7_7") (pintype "passive"))
    )
    (net (code "70") (name "unconnected-(JP1-Pad8)") (class "Default")
      (node (ref "JP1") (pin "8") (pinfunction "8_8") (pintype "passive"))
    )
    (net (code "71") (name "unconnected-(JP1-Pad9)") (class "Default")
      (node (ref "JP1") (pin "9") (pinfunction "9_9") (pintype "passive"))
    )
    (net (code "72") (name "unconnected-(JP1-Pad10)") (class "Default")
      (node (ref "JP1") (pin "10") (pinfunction "10_10") (pintype "passive"))
    )
    (net (code "73") (name "unconnected-(JP1-Pad11)") (class "Default")
      (node (ref "JP1") (pin "11") (pinfunction "11_11") (pintype "passive"))
    )
    (net (code "74") (name "unconnected-(JP2-Pad1)") (class "Default")
      (node (ref "JP2") (pin "1") (pinfunction "1_1") (pintype "passive"))
    )
    (net (code "75") (name "unconnected-(JP2-Pad2)") (class "Default")
      (node (ref "JP2") (pin "2") (pinfunction "2_2") (pintype "passive"))
    )
    (net (code "76") (name "unconnected-(JP2-Pad3)") (class "Default")
      (node (ref "JP2") (pin "3") (pinfunction "3_3") (pintype "passive"))
    )
    (net (code "77") (name "unconnected-(JP2-Pad4)") (class "Default")
      (node (ref "JP2") (pin "4") (pinfunction "4_4") (pintype "passive"))
    )
    (net (code "78") (name "unconnected-(JP2-Pad5)") (class "Default")
      (node (ref "JP2") (pin "5") (pinfunction "5_5") (pintype "passive"))
    )
    (net (code "79") (name "unconnected-(JP2-Pad6)") (class "Default")
      (node (ref "JP2") (pin "6") (pinfunction "6_6") (pintype "passive"))
    )
    (net (code "80") (name "unconnected-(JP2-Pad7)") (class "Default")
      (node (ref "JP2") (pin "7") (pinfunction "7_7") (pintype "passive"))
    )
    (net (code "81") (name "unconnected-(JP2-Pad8)") (class "Default")
      (node (ref "JP2") (pin "8") (pinfunction "8_8") (pintype "passive"))
    )
    (net (code "82") (name "unconnected-(JP2-Pad9)") (class "Default")
      (node (ref "JP2") (pin "9") (pinfunction "9_9") (pintype "passive"))
    )
    (net (code "83") (name "unconnected-(JP2-Pad10)") (class "Default")
      (node (ref "JP2") (pin "10") (pinfunction "10_10") (pintype "passive"))
    )
    (net (code "84") (name "unconnected-(JP2-Pad11)") (class "Default")
      (node (ref "JP2") (pin "11") (pinfunction "11_11") (pintype "passive"))
    )
    (net (code "85") (name "unconnected-(JP2-Pad12)") (class "Default")
      (node (ref "JP2") (pin "12") (pinfunction "12_12") (pintype "passive"))
    )
    (net (code "86") (name "unconnected-(JP2-Pad13)") (class "Default")
      (node (ref "JP2") (pin "13") (pinfunction "13_13") (pintype "passive"))
    )
    (net (code "87") (name "unconnected-(JP2-Pad14)") (class "Default")
      (node (ref "JP2") (pin "14") (pinfunction "14_14") (pintype "passive"))
    )
    (net (code "88") (name "unconnected-(JP2-Pad15)") (class "Default")
      (node (ref "JP2") (pin "15") (pinfunction "15_15") (pintype "passive"))
    )
    (net (code "89") (name "unconnected-(JP2-Pad16)") (class "Default")
      (node (ref "JP2") (pin "16") (pinfunction "16_16") (pintype "passive"))
    )
    (net (code "90") (name "unconnected-(JP3-D+-PadD+1)") (class "Default")
      (node (ref "JP3") (pin "D+1") (pinfunction "D+_D+1") (pintype "bidirectional"))
    )
    (net (code "91") (name "unconnected-(JP3-D--PadD-1)") (class "Default")
      (node (ref "JP3") (pin "D-1") (pinfunction "D-_D-1") (pintype "bidirectional"))
    )
    (net (code "92") (name "unconnected-(JP15-Pad1)") (class "Default")
      (node (ref "JP15") (pin "1") (pinfunction "1_1") (pintype "passive"))
    )
    (net (code "93") (name "unconnected-(JP15-Pad2)") (class "Default")
      (node (ref "JP15") (pin "2") (pinfunction "2_2") (pintype "passive"))
    )
    (net (code "94") (name "unconnected-(JP15-Pad3)") (class "Default")
      (node (ref "JP15") (pin "3") (pinfunction "3_3") (pintype "passive"))
    )
    (net (code "95") (name "unconnected-(JP15-Pad4)") (class "Default")
      (node (ref "JP15") (pin "4") (pinfunction "4_4") (pintype "passive"))
    )
    (net (code "96") (name "unconnected-(JP15-Pad5)") (class "Default")
      (node (ref "JP15") (pin "5") (pinfunction "5_5") (pintype "passive"))
    )
    (net (code "97") (name "unconnected-(JP15-Pad6)") (class "Default")
      (node (ref "JP15") (pin "6") (pinfunction "6_6") (pintype "passive"))
    )
    (net (code "98") (name "unconnected-(JP15-Pad7)") (class "Default")
      (node (ref "JP15") (pin "7") (pinfunction "7_7") (pintype "passive"))
    )
    (net (code "99") (name "unconnected-(JP15-Pad8)") (class "Default")
      (node (ref "JP15") (pin "8") (pinfunction "8_8") (pintype "passive"))
    )
    (net (code "100") (name "unconnected-(JP15-Pad9)") (class "Default")
      (node (ref "JP15") (pin "9") (pinfunction "9_9") (pintype "passive"))
    )
    (net (code "101") (name "unconnected-(JP15-Pad10)") (class "Default")
      (node (ref "JP15") (pin "10") (pinfunction "10_10") (pintype "passive"))
    )
    (net (code "102") (name "unconnected-(JP15-Pad11)") (class "Default")
      (node (ref "JP15") (pin "11") (pinfunction "11_11") (pintype "passive"))
    )
    (net (code "103") (name "unconnected-(JP15-Pad12)") (class "Default")
      (node (ref "JP15") (pin "12") (pinfunction "12_12") (pintype "passive"))
    )
    (net (code "104") (name "unconnected-(JP15-Pad13)") (class "Default")
      (node (ref "JP15") (pin "13") (pinfunction "13_13") (pintype "passive"))
    )
    (net (code "105") (name "unconnected-(JP15-Pad14)") (class "Default")
      (node (ref "JP15") (pin "14") (pinfunction "14_14") (pintype "passive"))
    )
    (net (code "106") (name "unconnected-(JP15-Pad15)") (class "Default")
      (node (ref "JP15") (pin "15") (pinfunction "15_15") (pintype "passive"))
    )
    (net (code "107") (name "unconnected-(JP15-Pad16)") (class "Default")
      (node (ref "JP15") (pin "16") (pinfunction "16_16") (pintype "passive"))
    )
    (net (code "108") (name "unconnected-(JP16-Pad2)") (class "Default")
      (node (ref "JP16") (pin "2") (pinfunction "2_2") (pintype "passive"))
    )
    (net (code "109") (name "unconnected-(JP16-Pad3)") (class "Default")
      (node (ref "JP16") (pin "3") (pinfunction "3_3") (pintype "passive"))
    )
    (net (code "110") (name "unconnected-(JP16-Pad4)") (class "Default")
      (node (ref "JP16") (pin "4") (pinfunction "4_4") (pintype "passive"))
    )
    (net (code "111") (name "unconnected-(JP16-Pad5)") (class "Default")
      (node (ref "JP16") (pin "5") (pinfunction "5_5") (pintype "passive"))
    )
    (net (code "112") (name "unconnected-(JP16-Pad6)") (class "Default")
      (node (ref "JP16") (pin "6") (pinfunction "6_6") (pintype "passive"))
    )
    (net (code "113") (name "unconnected-(JP16-Pad7)") (class "Default")
      (node (ref "JP16") (pin "7") (pinfunction "7_7") (pintype "passive"))
    )
    (net (code "114") (name "unconnected-(JP16-Pad8)") (class "Default")
      (node (ref "JP16") (pin "8") (pinfunction "8_8") (pintype "passive"))
    )
    (net (code "115") (name "unconnected-(JP16-Pad9)") (class "Default")
      (node (ref "JP16") (pin "9") (pinfunction "9_9") (pintype "passive"))
    )
    (net (code "116") (name "unconnected-(JP16-Pad10)") (class "Default")
      (node (ref "JP16") (pin "10") (pinfunction "10_10") (pintype "passive"))
    )
    (net (code "117") (name "unconnected-(JP16-Pad11)") (class "Default")
      (node (ref "JP16") (pin "11") (pinfunction "11_11") (pintype "passive"))
    )
    (net (code "118") (name "unconnected-(JP17-Pad2)") (class "Default")
      (node (ref "JP17") (pin "2") (pinfunction "2_2") (pintype "passive"))
    )
    (net (code "119") (name "unconnected-(JP17-Pad3)") (class "Default")
      (node (ref "JP17") (pin "3") (pinfunction "3_3") (pintype "passive"))
    )
    (net (code "120") (name "unconnected-(JP17-Pad4)") (class "Default")
      (node (ref "JP17") (pin "4") (pinfunction "4_4") (pintype "passive"))
    )
    (net (code "121") (name "unconnected-(JP17-Pad5)") (class "Default")
      (node (ref "JP17") (pin "5") (pinfunction "5_5") (pintype "passive"))
    )
    (net (code "122") (name "unconnected-(JP17-Pad6)") (class "Default")
      (node (ref "JP17") (pin "6") (pinfunction "6_6") (pintype "passive"))
    )
    (net (code "123") (name "unconnected-(JP17-Pad7)") (class "Default")
      (node (ref "JP17") (pin "7") (pinfunction "7_7") (pintype "passive"))
    )
    (net (code "124") (name "unconnected-(JP17-Pad8)") (class "Default")
      (node (ref "JP17") (pin "8") (pinfunction "8_8") (pintype "passive"))
    )
    (net (code "125") (name "unconnected-(JP17-Pad9)") (class "Default")
      (node (ref "JP17") (pin "9") (pinfunction "9_9") (pintype "passive"))
    )
    (net (code "126") (name "unconnected-(JP17-Pad10)") (class "Default")
      (node (ref "JP17") (pin "10") (pinfunction "10_10") (pintype "passive"))
    )
    (net (code "127") (name "unconnected-(JP17-Pad11)") (class "Default")
      (node (ref "JP17") (pin "11") (pinfunction "11_11") (pintype "passive"))
    )
    (net (code "128") (name "unconnected-(JP18-Pad2)") (class "Default")
      (node (ref "JP18") (pin "2") (pinfunction "2_2") (pintype "passive"))
    )
    (net (code "129") (name "unconnected-(JP18-Pad3)") (class "Default")
      (node (ref "JP18") (pin "3") (pinfunction "3_3") (pintype "passive"))
    )
    (net (code "130") (name "unconnected-(JP18-Pad4)") (class "Default")
      (node (ref "JP18") (pin "4") (pinfunction "4_4") (pintype "passive"))
    )
    (net (code "131") (name "unconnected-(JP18-Pad5)") (class "Default")
      (node (ref "JP18") (pin "5") (pinfunction "5_5") (pintype "passive"))
    )
    (net (code "132") (name "unconnected-(JP18-Pad6)") (class "Default")
      (node (ref "JP18") (pin "6") (pinfunction "6_6") (pintype "passive"))
    )
    (net (code "133") (name "unconnected-(JP18-Pad7)") (class "Default")
      (node (ref "JP18") (pin "7") (pinfunction "7_7") (pintype "passive"))
    )
    (net (code "134") (name "unconnected-(JP18-Pad8)") (class "Default")
      (node (ref "JP18") (pin "8") (pinfunction "8_8") (pintype "passive"))
    )
    (net (code "135") (name "unconnected-(JP18-Pad9)") (class "Default")
      (node (ref "JP18") (pin "9") (pinfunction "9_9") (pintype "passive"))
    )
    (net (code "136") (name "unconnected-(JP18-Pad10)") (class "Default")
      (node (ref "JP18") (pin "10") (pinfunction "10_10") (pintype "passive"))
    )
    (net (code "137") (name "unconnected-(JP18-Pad11)") (class "Default")
      (node (ref "JP18") (pin "11") (pinfunction "11_11") (pintype "passive"))
    )
    (net (code "138") (name "unconnected-(JP19-Pad2)") (class "Default")
      (node (ref "JP19") (pin "2") (pinfunction "2_2") (pintype "passive"))
    )
    (net (code "139") (name "unconnected-(JP19-Pad3)") (class "Default")
      (node (ref "JP19") (pin "3") (pinfunction "3_3") (pintype "passive"))
    )
    (net (code "140") (name "unconnected-(JP19-Pad4)") (class "Default")
      (node (ref "JP19") (pin "4") (pinfunction "4_4") (pintype "passive"))
    )
    (net (code "141") (name "unconnected-(JP19-Pad5)") (class "Default")
      (node (ref "JP19") (pin "5") (pinfunction "5_5") (pintype "passive"))
    )
    (net (code "142") (name "unconnected-(JP19-Pad6)") (class "Default")
      (node (ref "JP19") (pin "6") (pinfunction "6_6") (pintype "passive"))
    )
    (net (code "143") (name "unconnected-(JP19-Pad7)") (class "Default")
      (node (ref "JP19") (pin "7") (pinfunction "7_7") (pintype "passive"))
    )
    (net (code "144") (name "unconnected-(JP19-Pad8)") (class "Default")
      (node (ref "JP19") (pin "8") (pinfunction "8_8") (pintype "passive"))
    )
    (net (code "145") (name "unconnected-(JP19-Pad9)") (class "Default")
      (node (ref "JP19") (pin "9") (pinfunction "9_9") (pintype "passive"))
    )
    (net (code "146") (name "unconnected-(JP19-Pad10)") (class "Default")
      (node (ref "JP19") (pin "10") (pinfunction "10_10") (pintype "passive"))
    )
    (net (code "147") (name "unconnected-(JP19-Pad11)") (class "Default")
      (node (ref "JP19") (pin "11") (pinfunction "11_11") (pintype "passive"))
    )
    (net (code "148") (name "unconnected-(JP20-Pad2)") (class "Default")
      (node (ref "JP20") (pin "2") (pinfunction "2_2") (pintype "passive"))
    )
    (net (code "149") (name "unconnected-(JP20-Pad3)") (class "Default")
      (node (ref "JP20") (pin "3") (pinfunction "3_3") (pintype "passive"))
    )
    (net (code "150") (name "unconnected-(JP20-Pad4)") (class "Default")
      (node (ref "JP20") (pin "4") (pinfunction "4_4") (pintype "passive"))
    )
    (net (code "151") (name "unconnected-(JP20-Pad5)") (class "Default")
      (node (ref "JP20") (pin "5") (pinfunction "5_5") (pintype "passive"))
    )
    (net (code "152") (name "unconnected-(JP20-Pad6)") (class "Default")
      (node (ref "JP20") (pin "6") (pinfunction "6_6") (pintype "passive"))
    )
    (net (code "153") (name "unconnected-(JP20-Pad7)") (class "Default")
      (node (ref "JP20") (pin "7") (pinfunction "7_7") (pintype "passive"))
    )
    (net (code "154") (name "unconnected-(JP20-Pad8)") (class "Default")
      (node (ref "JP20") (pin "8") (pinfunction "8_8") (pintype "passive"))
    )
    (net (code "155") (name "unconnected-(JP20-Pad9)") (class "Default")
      (node (ref "JP20") (pin "9") (pinfunction "9_9") (pintype "passive"))
    )
    (net (code "156") (name "unconnected-(JP20-Pad10)") (class "Default")
      (node (ref "JP20") (pin "10") (pinfunction "10_10") (pintype "passive"))
    )
    (net (code "157") (name "unconnected-(JP20-Pad11)") (class "Default")
      (node (ref "JP20") (pin "11") (pinfunction "11_11") (pintype "passive"))
    )
    (net (code "158") (name "unconnected-(JP21-Pad2)") (class "Default")
      (node (ref "JP21") (pin "2") (pinfunction "2_2") (pintype "passive"))
    )
    (net (code "159") (name "unconnected-(JP21-Pad3)") (class "Default")
      (node (ref "JP21") (pin "3") (pinfunction "3_3") (pintype "passive"))
    )
    (net (code "160") (name "unconnected-(JP21-Pad4)") (class "Default")
      (node (ref "JP21") (pin "4") (pinfunction "4_4") (pintype "passive"))
    )
    (net (code "161") (name "unconnected-(JP21-Pad5)") (class "Default")
      (node (ref "JP21") (pin "5") (pinfunction "5_5") (pintype "passive"))
    )
    (net (code "162") (name "unconnected-(JP21-Pad6)") (class "Default")
      (node (ref "JP21") (pin "6") (pinfunction "6_6") (pintype "passive"))
    )
    (net (code "163") (name "unconnected-(JP21-Pad7)") (class "Default")
      (node (ref "JP21") (pin "7") (pinfunction "7_7") (pintype "passive"))
    )
    (net (code "164") (name "unconnected-(JP21-Pad8)") (class "Default")
      (node (ref "JP21") (pin "8") (pinfunction "8_8") (pintype "passive"))
    )
    (net (code "165") (name "unconnected-(JP21-Pad9)") (class "Default")
      (node (ref "JP21") (pin "9") (pinfunction "9_9") (pintype "passive"))
    )
    (net (code "166") (name "unconnected-(JP21-Pad10)") (class "Default")
      (node (ref "JP21") (pin "10") (pinfunction "10_10") (pintype "passive"))
    )
    (net (code "167") (name "unconnected-(JP21-Pad11)") (class "Default")
      (node (ref "JP21") (pin "11") (pinfunction "11_11") (pintype "passive"))
    )
    (net (code "168") (name "unconnected-(JP22-Pad2)") (class "Default")
      (node (ref "JP22") (pin "2") (pinfunction "2_2") (pintype "passive"))
    )
    (net (code "169") (name "unconnected-(JP22-Pad3)") (class "Default")
      (node (ref "JP22") (pin "3") (pinfunction "3_3") (pintype "passive"))
    )
    (net (code "170") (name "unconnected-(JP22-Pad4)") (class "Default")
      (node (ref "JP22") (pin "4") (pinfunction "4_4") (pintype "passive"))
    )
    (net (code "171") (name "unconnected-(JP22-Pad5)") (class "Default")
      (node (ref "JP22") (pin "5") (pinfunction "5_5") (pintype "passive"))
    )
    (net (code "172") (name "unconnected-(JP22-Pad6)") (class "Default")
      (node (ref "JP22") (pin "6") (pinfunction "6_6") (pintype "passive"))
    )
    (net (code "173") (name "unconnected-(JP22-Pad7)") (class "Default")
      (node (ref "JP22") (pin "7") (pinfunction "7_7") (pintype "passive"))
    )
    (net (code "174") (name "unconnected-(JP22-Pad8)") (class "Default")
      (node (ref "JP22") (pin "8") (pinfunction "8_8") (pintype "passive"))
    )
    (net (code "175") (name "unconnected-(JP22-Pad9)") (class "Default")
      (node (ref "JP22") (pin "9") (pinfunction "9_9") (pintype "passive"))
    )
    (net (code "176") (name "unconnected-(JP22-Pad10)") (class "Default")
      (node (ref "JP22") (pin "10") (pinfunction "10_10") (pintype "passive"))
    )
    (net (code "177") (name "unconnected-(JP22-Pad11)") (class "Default")
      (node (ref "JP22") (pin "11") (pinfunction "11_11") (pintype "passive"))
    )
    (net (code "178") (name "unconnected-(JP203-Pad1)") (class "Default")
      (node (ref "JP203") (pin "1") (pinfunction "1_1") (pintype "passive"))
    )
    (net (code "179") (name "unconnected-(JP203-Pad2)") (class "Default")
      (node (ref "JP203") (pin "2") (pinfunction "2_2") (pintype "passive"))
    )
    (net (code "180") (name "unconnected-(JP203-Pad3)") (class "Default")
      (node (ref "JP203") (pin "3") (pinfunction "3_3") (pintype "passive"))
    )
    (net (code "181") (name "unconnected-(JP203-Pad4)") (class "Default")
      (node (ref "JP203") (pin "4") (pinfunction "4_4") (pintype "passive"))
    )
    (net (code "182") (name "unconnected-(JP203-Pad5)") (class "Default")
      (node (ref "JP203") (pin "5") (pinfunction "5_5") (pintype "passive"))
    )
    (net (code "183") (name "unconnected-(JP203-Pad6)") (class "Default")
      (node (ref "JP203") (pin "6") (pinfunction "6_6") (pintype "passive"))
    )
    (net (code "184") (name "unconnected-(JP203-Pad7)") (class "Default")
      (node (ref "JP203") (pin "7") (pinfunction "7_7") (pintype "passive"))
    )
    (net (code "185") (name "unconnected-(JP203-Pad8)") (class "Default")
      (node (ref "JP203") (pin "8") (pinfunction "8_8") (pintype "passive"))
    )
    (net (code "186") (name "unconnected-(JP203-Pad9)") (class "Default")
      (node (ref "JP203") (pin "9") (pinfunction "9_9") (pintype "passive"))
    )
    (net (code "187") (name "unconnected-(JP203-Pad10)") (class "Default")
      (node (ref "JP203") (pin "10") (pinfunction "10_10") (pintype "passive"))
    )
    (net (code "188") (name "unconnected-(JP203-Pad11)") (class "Default")
      (node (ref "JP203") (pin "11") (pinfunction "11_11") (pintype "passive"))
    )
    (net (code "189") (name "unconnected-(JP203-Pad12)") (class "Default")
      (node (ref "JP203") (pin "12") (pinfunction "12_12") (pintype "passive"))
    )
    (net (code "190") (name "unconnected-(JP203-Pad13)") (class "Default")
      (node (ref "JP203") (pin "13") (pinfunction "13_13") (pintype "passive"))
    )
    (net (code "191") (name "unconnected-(JP203-Pad14)") (class "Default")
      (node (ref "JP203") (pin "14") (pinfunction "14_14") (pintype "passive"))
    )
    (net (code "192") (name "unconnected-(JP203-Pad15)") (class "Default")
      (node (ref "JP203") (pin "15") (pinfunction "15_15") (pintype "passive"))
    )
    (net (code "193") (name "unconnected-(JP203-Pad16)") (class "Default")
      (node (ref "JP203") (pin "16") (pinfunction "16_16") (pintype "passive"))
    )
    (net (code "194") (name "unconnected-(JP204-Pad1)") (class "Default")
      (node (ref "JP204") (pin "1") (pinfunction "1_1") (pintype "passive"))
    )
    (net (code "195") (name "unconnected-(JP204-Pad2)") (class "Default")
      (node (ref "JP204") (pin "2") (pinfunction "2_2") (pintype "passive"))
    )
    (net (code "196") (name "unconnected-(JP204-Pad3)") (class "Default")
      (node (ref "JP204") (pin "3") (pinfunction "3_3") (pintype "passive"))
    )
    (net (code "197") (name "unconnected-(JP204-Pad4)") (class "Default")
      (node (ref "JP204") (pin "4") (pinfunction "4_4") (pintype "passive"))
    )
    (net (code "198") (name "unconnected-(JP204-Pad5)") (class "Default")
      (node (ref "JP204") (pin "5") (pinfunction "5_5") (pintype "passive"))
    )
    (net (code "199") (name "unconnected-(JP204-Pad6)") (class "Default")
      (node (ref "JP204") (pin "6") (pinfunction "6_6") (pintype "passive"))
    )
    (net (code "200") (name "unconnected-(JP204-Pad7)") (class "Default")
      (node (ref "JP204") (pin "7") (pinfunction "7_7") (pintype "passive"))
    )
    (net (code "201") (name "unconnected-(JP204-Pad8)") (class "Default")
      (node (ref "JP204") (pin "8") (pinfunction "8_8") (pintype "passive"))
    )
    (net (code "202") (name "unconnected-(JP204-Pad9)") (class "Default")
      (node (ref "JP204") (pin "9") (pinfunction "9_9") (pintype "passive"))
    )
    (net (code "203") (name "unconnected-(JP204-Pad10)") (class "Default")
      (node (ref "JP204") (pin "10") (pinfunction "10_10") (pintype "passive"))
    )
    (net (code "204") (name "unconnected-(JP204-Pad11)") (class "Default")
      (node (ref "JP204") (pin "11") (pinfunction "11_11") (pintype "passive"))
    )
    (net (code "205") (name "unconnected-(JP204-Pad12)") (class "Default")
      (node (ref "JP204") (pin "12") (pinfunction "12_12") (pintype "passive"))
    )
    (net (code "206") (name "unconnected-(JP204-Pad13)") (class "Default")
      (node (ref "JP204") (pin "13") (pinfunction "13_13") (pintype "passive"))
    )
    (net (code "207") (name "unconnected-(JP204-Pad14)") (class "Default")
      (node (ref "JP204") (pin "14") (pinfunction "14_14") (pintype "passive"))
    )
    (net (code "208") (name "unconnected-(JP204-Pad15)") (class "Default")
      (node (ref "JP204") (pin "15") (pinfunction "15_15") (pintype "passive"))
    )
    (net (code "209") (name "unconnected-(JP204-Pad16)") (class "Default")
      (node (ref "JP204") (pin "16") (pinfunction "16_16") (pintype "passive"))
    )
    (net (code "210") (name "unconnected-(JP213-Pad1)") (class "Default")
      (node (ref "JP213") (pin "1") (pinfunction "1_1") (pintype "passive"))
    )
    (net (code "211") (name "unconnected-(JP213-Pad2)") (class "Default")
      (node (ref "JP213") (pin "2") (pinfunction "2_2") (pintype "passive"))
    )
    (net (code "212") (name "unconnected-(JP213-Pad3)") (class "Default")
      (node (ref "JP213") (pin "3") (pinfunction "3_3") (pintype "passive"))
    )
    (net (code "213") (name "unconnected-(JP213-Pad4)") (class "Default")
      (node (ref "JP213") (pin "4") (pinfunction "4_4") (pintype "passive"))
    )
    (net (code "214") (name "unconnected-(JP213-Pad5)") (class "Default")
      (node (ref "JP213") (pin "5") (pinfunction "5_5") (pintype "passive"))
    )
    (net (code "215") (name "unconnected-(JP213-Pad6)") (class "Default")
      (node (ref "JP213") (pin "6") (pinfunction "6_6") (pintype "passive"))
    )
    (net (code "216") (name "unconnected-(JP213-Pad7)") (class "Default")
      (node (ref "JP213") (pin "7") (pinfunction "7_7") (pintype "passive"))
    )
    (net (code "217") (name "unconnected-(JP213-Pad8)") (class "Default")
      (node (ref "JP213") (pin "8") (pinfunction "8_8") (pintype "passive"))
    )
    (net (code "218") (name "unconnected-(JP213-Pad9)") (class "Default")
      (node (ref "JP213") (pin "9") (pinfunction "9_9") (pintype "passive"))
    )
    (net (code "219") (name "unconnected-(JP213-Pad10)") (class "Default")
      (node (ref "JP213") (pin "10") (pinfunction "10_10") (pintype "passive"))
    )
    (net (code "220") (name "unconnected-(JP213-Pad11)") (class "Default")
      (node (ref "JP213") (pin "11") (pinfunction "11_11") (pintype "passive"))
    )
    (net (code "221") (name "unconnected-(JP213-Pad12)") (class "Default")
      (node (ref "JP213") (pin "12") (pinfunction "12_12") (pintype "passive"))
    )
    (net (code "222") (name "unconnected-(JP213-Pad13)") (class "Default")
      (node (ref "JP213") (pin "13") (pinfunction "13_13") (pintype "passive"))
    )
    (net (code "223") (name "unconnected-(JP213-Pad14)") (class "Default")
      (node (ref "JP213") (pin "14") (pinfunction "14_14") (pintype "passive"))
    )
    (net (code "224") (name "unconnected-(JP213-Pad15)") (class "Default")
      (node (ref "JP213") (pin "15") (pinfunction "15_15") (pintype "passive"))
    )
    (net (code "225") (name "unconnected-(JP213-Pad16)") (class "Default")
      (node (ref "JP213") (pin "16") (pinfunction "16_16") (pintype "passive"))
    )
    (net (code "226") (name "unconnected-(JP214-Pad1)") (class "Default")
      (node (ref "JP214") (pin "1") (pinfunction "1_1") (pintype "passive"))
    )
    (net (code "227") (name "unconnected-(JP214-Pad2)") (class "Default")
      (node (ref "JP214") (pin "2") (pinfunction "2_2") (pintype "passive"))
    )
    (net (code "228") (name "unconnected-(JP214-Pad3)") (class "Default")
      (node (ref "JP214") (pin "3") (pinfunction "3_3") (pintype "passive"))
    )
    (net (code "229") (name "unconnected-(JP214-Pad4)") (class "Default")
      (node (ref "JP214") (pin "4") (pinfunction "4_4") (pintype "passive"))
    )
    (net (code "230") (name "unconnected-(JP214-Pad5)") (class "Default")
      (node (ref "JP214") (pin "5") (pinfunction "5_5") (pintype "passive"))
    )
    (net (code "231") (name "unconnected-(JP214-Pad6)") (class "Default")
      (node (ref "JP214") (pin "6") (pinfunction "6_6") (pintype "passive"))
    )
    (net (code "232") (name "unconnected-(JP214-Pad7)") (class "Default")
      (node (ref "JP214") (pin "7") (pinfunction "7_7") (pintype "passive"))
    )
    (net (code "233") (name "unconnected-(JP214-Pad8)") (class "Default")
      (node (ref "JP214") (pin "8") (pinfunction "8_8") (pintype "passive"))
    )
    (net (code "234") (name "unconnected-(JP214-Pad9)") (class "Default")
      (node (ref "JP214") (pin "9") (pinfunction "9_9") (pintype "passive"))
    )
    (net (code "235") (name "unconnected-(JP214-Pad10)") (class "Default")
      (node (ref "JP214") (pin "10") (pinfunction "10_10") (pintype "passive"))
    )
    (net (code "236") (name "unconnected-(JP214-Pad11)") (class "Default")
      (node (ref "JP214") (pin "11") (pinfunction "11_11") (pintype "passive"))
    )
    (net (code "237") (name "unconnected-(JP214-Pad12)") (class "Default")
      (node (ref "JP214") (pin "12") (pinfunction "12_12") (pintype "passive"))
    )
    (net (code "238") (name "unconnected-(JP214-Pad13)") (class "Default")
      (node (ref "JP214") (pin "13") (pinfunction "13_13") (pintype "passive"))
    )
    (net (code "239") (name "unconnected-(JP214-Pad14)") (class "Default")
      (node (ref "JP214") (pin "14") (pinfunction "14_14") (pintype "passive"))
    )
    (net (code "240") (name "unconnected-(JP214-Pad15)") (class "Default")
      (node (ref "JP214") (pin "15") (pinfunction "15_15") (pintype "passive"))
    )
    (net (code "241") (name "unconnected-(JP214-Pad16)") (class "Default")
      (node (ref "JP214") (pin "16") (pinfunction "16_16") (pintype "passive"))
    )
  )
)
